# ppc_power.net
KiCad netlist of a schematic drawn in Altium Designer
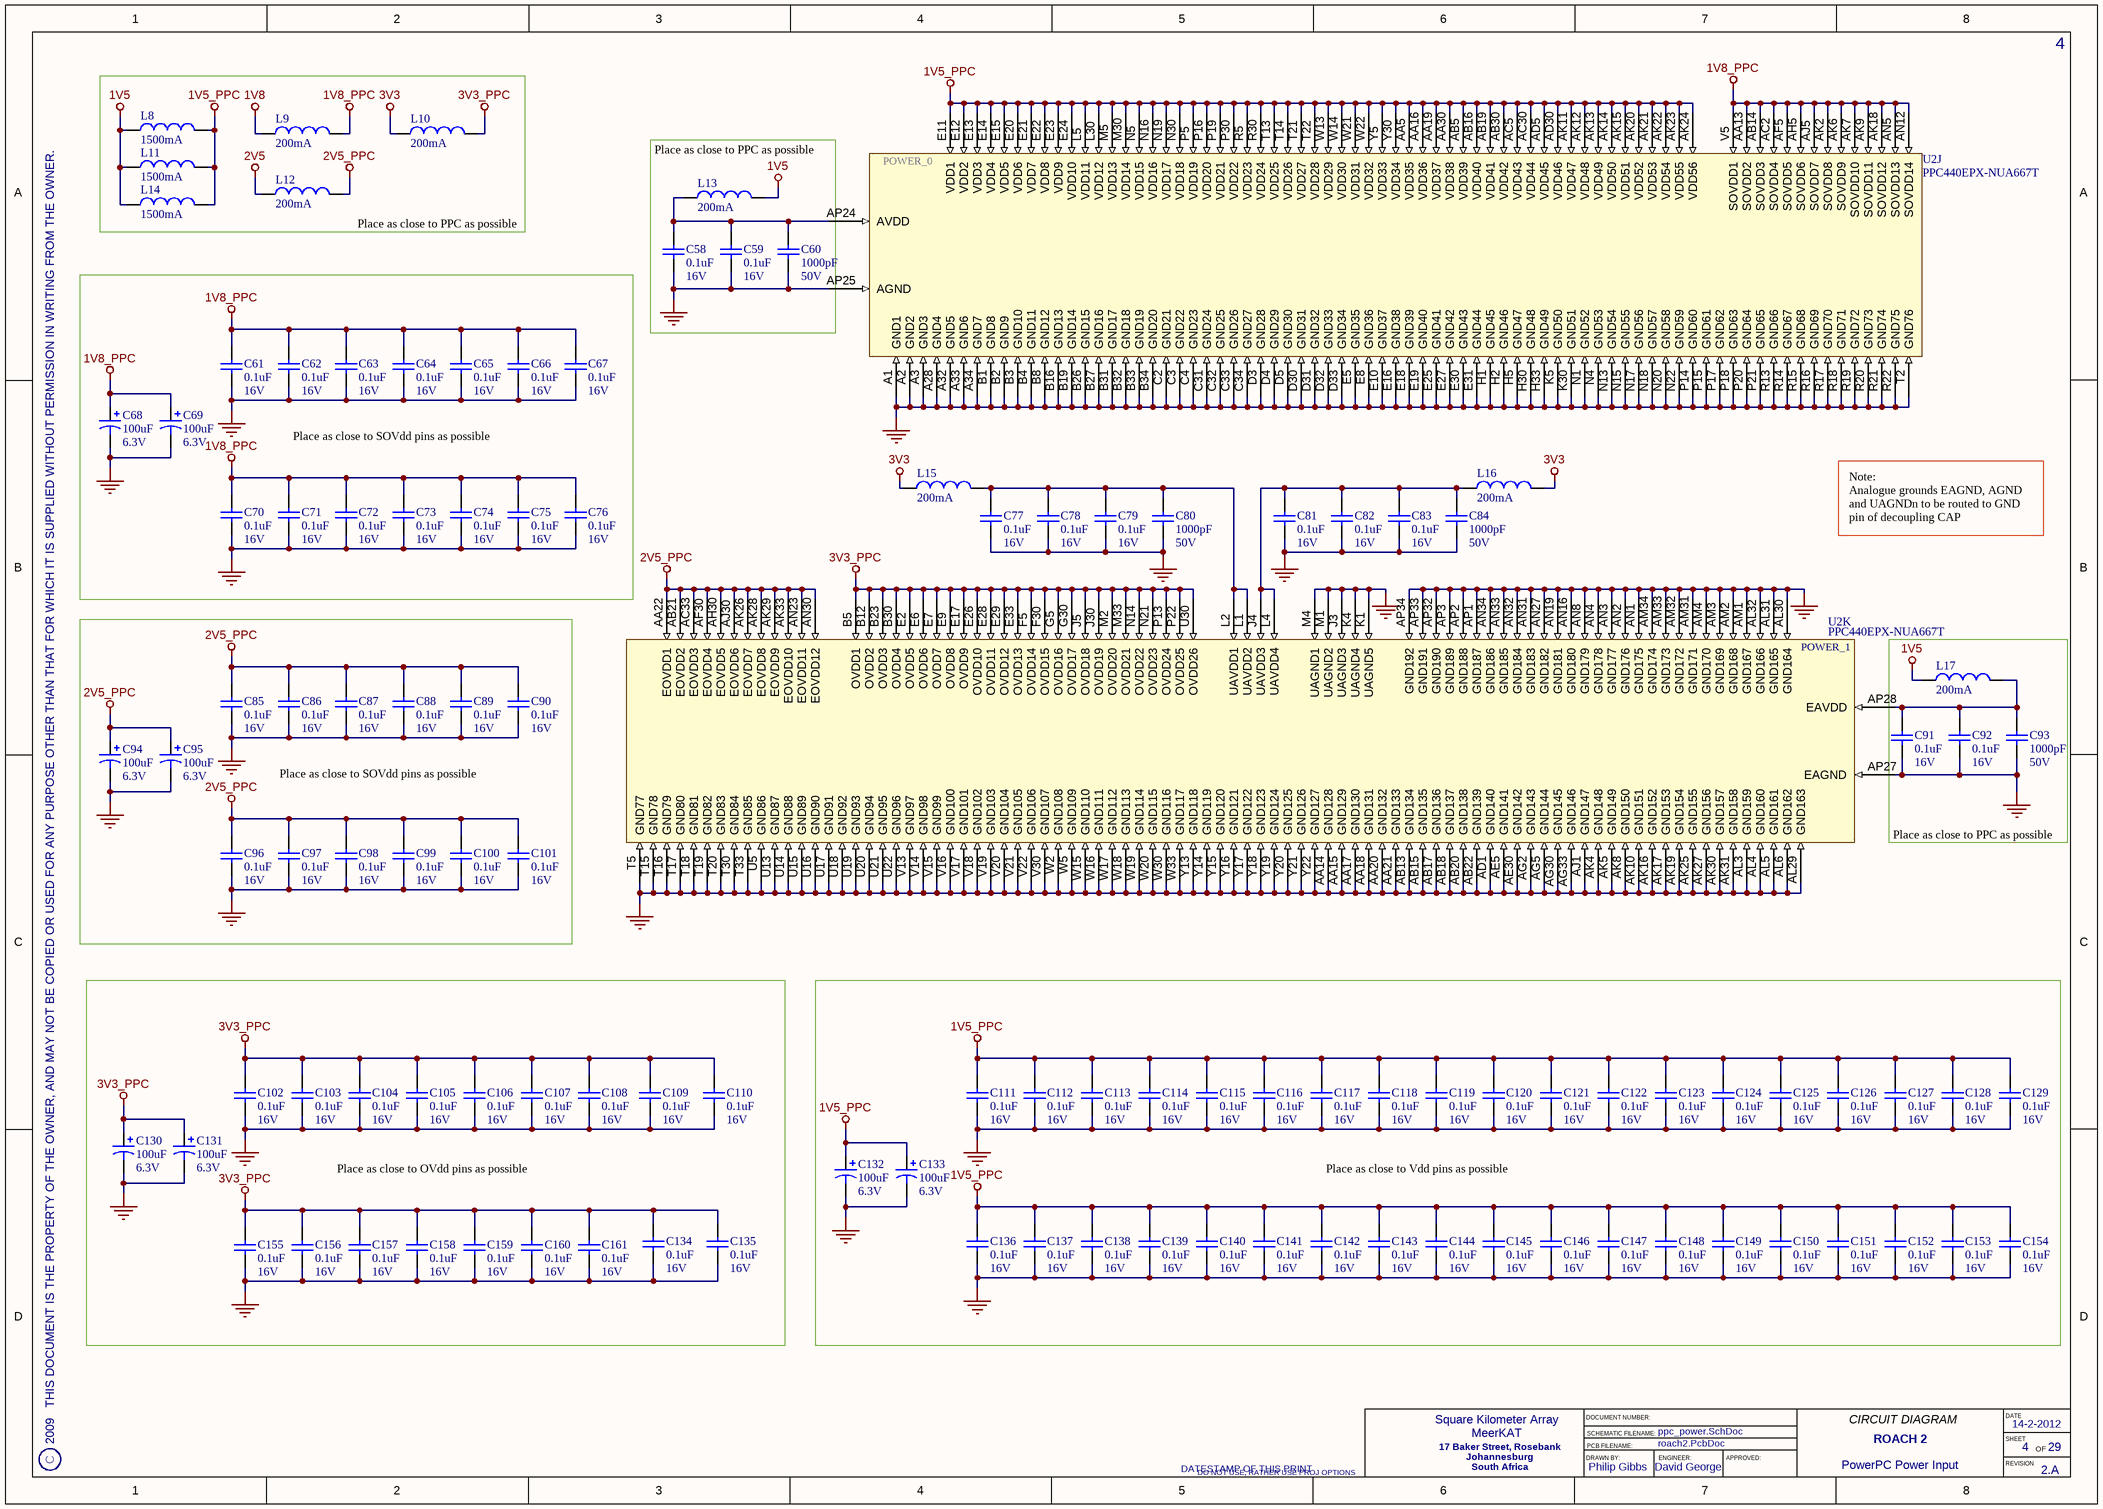
[diagram p0: ppc_power.SchDoc]

(export (version "E")
  (design (tool "Eeschema 10.0.6"))
  (components
    (comp (ref "C58")
      (value "0.1uF")
      (footprint "CAPC1005X60L")
      (description "0.1uF, Ceramic Capacitor")
      (fields
        (field (name "RATING") "16V")
        (field (name "MANUFACTURER") "VENKEL")
        (field (name "PARTNUM") "C0402X7R160-104KN")
      )
      (libsource (lib "altium_db") (part "CapStd"))
    )
    (comp (ref "C59")
      (value "0.1uF")
      (footprint "CAPC1005X60L")
      (description "0.1uF, Ceramic Capacitor")
      (fields
        (field (name "RATING") "16V")
        (field (name "MANUFACTURER") "VENKEL")
        (field (name "PARTNUM") "C0402X7R160-104KN")
      )
      (libsource (lib "altium_db") (part "CapStd"))
    )
    (comp (ref "C60")
      (value "1000pF")
      (footprint "CAPC1005X55L")
      (description "1000pF, Ceramic Capacitor")
      (fields
        (field (name "RATING") "50V")
        (field (name "MANUFACTURER") "MURATA")
        (field (name "PARTNUM") "GRM155R61H102KA01D")
      )
      (libsource (lib "altium_db") (part "CapStd"))
    )
    (comp (ref "C61")
      (value "0.1uF")
      (footprint "CAPC1005X60L")
      (description "0.1uF, Ceramic Capacitor")
      (fields
        (field (name "RATING") "16V")
        (field (name "MANUFACTURER") "VENKEL")
        (field (name "PARTNUM") "C0402X7R160-104KN")
      )
      (libsource (lib "altium_db") (part "CapStd"))
    )
    (comp (ref "C62")
      (value "0.1uF")
      (footprint "CAPC1005X60L")
      (description "0.1uF, Ceramic Capacitor")
      (fields
        (field (name "RATING") "16V")
        (field (name "MANUFACTURER") "VENKEL")
        (field (name "PARTNUM") "C0402X7R160-104KN")
      )
      (libsource (lib "altium_db") (part "CapStd"))
    )
    (comp (ref "C63")
      (value "0.1uF")
      (footprint "CAPC1005X60L")
      (description "0.1uF, Ceramic Capacitor")
      (fields
        (field (name "RATING") "16V")
        (field (name "MANUFACTURER") "VENKEL")
        (field (name "PARTNUM") "C0402X7R160-104KN")
      )
      (libsource (lib "altium_db") (part "CapStd"))
    )
    (comp (ref "C64")
      (value "0.1uF")
      (footprint "CAPC1005X60L")
      (description "0.1uF, Ceramic Capacitor")
      (fields
        (field (name "RATING") "16V")
        (field (name "MANUFACTURER") "VENKEL")
        (field (name "PARTNUM") "C0402X7R160-104KN")
      )
      (libsource (lib "altium_db") (part "CapStd"))
    )
    (comp (ref "C65")
      (value "0.1uF")
      (footprint "CAPC1005X60L")
      (description "0.1uF, Ceramic Capacitor")
      (fields
        (field (name "RATING") "16V")
        (field (name "MANUFACTURER") "VENKEL")
        (field (name "PARTNUM") "C0402X7R160-104KN")
      )
      (libsource (lib "altium_db") (part "CapStd"))
    )
    (comp (ref "C66")
      (value "0.1uF")
      (footprint "CAPC1005X60L")
      (description "0.1uF, Ceramic Capacitor")
      (fields
        (field (name "RATING") "16V")
        (field (name "MANUFACTURER") "VENKEL")
        (field (name "PARTNUM") "C0402X7R160-104KN")
      )
      (libsource (lib "altium_db") (part "CapStd"))
    )
    (comp (ref "C67")
      (value "0.1uF")
      (footprint "CAPC1005X60L")
      (description "0.1uF, Ceramic Capacitor")
      (fields
        (field (name "RATING") "16V")
        (field (name "MANUFACTURER") "VENKEL")
        (field (name "PARTNUM") "C0402X7R160-104KN")
      )
      (libsource (lib "altium_db") (part "CapStd"))
    )
    (comp (ref "C68")
      (value "100uF")
      (footprint "CAPMP3528X210L")
      (description "100uF, Low ESR, Tantalum Capacitor")
      (fields
        (field (name "RATING") "6.3V")
        (field (name "MANUFACTURER") "AVX")
        (field (name "PARTNUM") "TPSB107M006R0200")
      )
      (libsource (lib "altium_db") (part "CapPol"))
    )
    (comp (ref "C69")
      (value "100uF")
      (footprint "CAPMP3528X210L")
      (description "100uF, Low ESR, Tantalum Capacitor")
      (fields
        (field (name "RATING") "6.3V")
        (field (name "MANUFACTURER") "AVX")
        (field (name "PARTNUM") "TPSB107M006R0200")
      )
      (libsource (lib "altium_db") (part "CapPol"))
    )
    (comp (ref "C70")
      (value "0.1uF")
      (footprint "CAPC1005X60L")
      (description "0.1uF, Ceramic Capacitor")
      (fields
        (field (name "RATING") "16V")
        (field (name "MANUFACTURER") "VENKEL")
        (field (name "PARTNUM") "C0402X7R160-104KN")
      )
      (libsource (lib "altium_db") (part "CapStd"))
    )
    (comp (ref "C71")
      (value "0.1uF")
      (footprint "CAPC1005X60L")
      (description "0.1uF, Ceramic Capacitor")
      (fields
        (field (name "RATING") "16V")
        (field (name "MANUFACTURER") "VENKEL")
        (field (name "PARTNUM") "C0402X7R160-104KN")
      )
      (libsource (lib "altium_db") (part "CapStd"))
    )
    (comp (ref "C72")
      (value "0.1uF")
      (footprint "CAPC1005X60L")
      (description "0.1uF, Ceramic Capacitor")
      (fields
        (field (name "RATING") "16V")
        (field (name "MANUFACTURER") "VENKEL")
        (field (name "PARTNUM") "C0402X7R160-104KN")
      )
      (libsource (lib "altium_db") (part "CapStd"))
    )
    (comp (ref "C73")
      (value "0.1uF")
      (footprint "CAPC1005X60L")
      (description "0.1uF, Ceramic Capacitor")
      (fields
        (field (name "RATING") "16V")
        (field (name "MANUFACTURER") "VENKEL")
        (field (name "PARTNUM") "C0402X7R160-104KN")
      )
      (libsource (lib "altium_db") (part "CapStd"))
    )
    (comp (ref "C74")
      (value "0.1uF")
      (footprint "CAPC1005X60L")
      (description "0.1uF, Ceramic Capacitor")
      (fields
        (field (name "RATING") "16V")
        (field (name "MANUFACTURER") "VENKEL")
        (field (name "PARTNUM") "C0402X7R160-104KN")
      )
      (libsource (lib "altium_db") (part "CapStd"))
    )
    (comp (ref "C75")
      (value "0.1uF")
      (footprint "CAPC1005X60L")
      (description "0.1uF, Ceramic Capacitor")
      (fields
        (field (name "RATING") "16V")
        (field (name "MANUFACTURER") "VENKEL")
        (field (name "PARTNUM") "C0402X7R160-104KN")
      )
      (libsource (lib "altium_db") (part "CapStd"))
    )
    (comp (ref "C76")
      (value "0.1uF")
      (footprint "CAPC1005X60L")
      (description "0.1uF, Ceramic Capacitor")
      (fields
        (field (name "RATING") "16V")
        (field (name "MANUFACTURER") "VENKEL")
        (field (name "PARTNUM") "C0402X7R160-104KN")
      )
      (libsource (lib "altium_db") (part "CapStd"))
    )
    (comp (ref "C77")
      (value "0.1uF")
      (footprint "CAPC1005X60L")
      (description "0.1uF, Ceramic Capacitor")
      (fields
        (field (name "RATING") "16V")
        (field (name "MANUFACTURER") "VENKEL")
        (field (name "PARTNUM") "C0402X7R160-104KN")
      )
      (libsource (lib "altium_db") (part "CapStd"))
    )
    (comp (ref "C78")
      (value "0.1uF")
      (footprint "CAPC1005X60L")
      (description "0.1uF, Ceramic Capacitor")
      (fields
        (field (name "RATING") "16V")
        (field (name "MANUFACTURER") "VENKEL")
        (field (name "PARTNUM") "C0402X7R160-104KN")
      )
      (libsource (lib "altium_db") (part "CapStd"))
    )
    (comp (ref "C79")
      (value "0.1uF")
      (footprint "CAPC1005X60L")
      (description "0.1uF, Ceramic Capacitor")
      (fields
        (field (name "RATING") "16V")
        (field (name "MANUFACTURER") "VENKEL")
        (field (name "PARTNUM") "C0402X7R160-104KN")
      )
      (libsource (lib "altium_db") (part "CapStd"))
    )
    (comp (ref "C80")
      (value "1000pF")
      (footprint "CAPC1005X55L")
      (description "1000pF, Ceramic Capacitor")
      (fields
        (field (name "RATING") "50V")
        (field (name "MANUFACTURER") "MURATA")
        (field (name "PARTNUM") "GRM155R61H102KA01D")
      )
      (libsource (lib "altium_db") (part "CapStd"))
    )
    (comp (ref "C81")
      (value "0.1uF")
      (footprint "CAPC1005X60L")
      (description "0.1uF, Ceramic Capacitor")
      (fields
        (field (name "RATING") "16V")
        (field (name "MANUFACTURER") "VENKEL")
        (field (name "PARTNUM") "C0402X7R160-104KN")
      )
      (libsource (lib "altium_db") (part "CapStd"))
    )
    (comp (ref "C82")
      (value "0.1uF")
      (footprint "CAPC1005X60L")
      (description "0.1uF, Ceramic Capacitor")
      (fields
        (field (name "RATING") "16V")
        (field (name "MANUFACTURER") "VENKEL")
        (field (name "PARTNUM") "C0402X7R160-104KN")
      )
      (libsource (lib "altium_db") (part "CapStd"))
    )
    (comp (ref "C83")
      (value "0.1uF")
      (footprint "CAPC1005X60L")
      (description "0.1uF, Ceramic Capacitor")
      (fields
        (field (name "RATING") "16V")
        (field (name "MANUFACTURER") "VENKEL")
        (field (name "PARTNUM") "C0402X7R160-104KN")
      )
      (libsource (lib "altium_db") (part "CapStd"))
    )
    (comp (ref "C84")
      (value "1000pF")
      (footprint "CAPC1005X55L")
      (description "1000pF, Ceramic Capacitor")
      (fields
        (field (name "RATING") "50V")
        (field (name "MANUFACTURER") "MURATA")
        (field (name "PARTNUM") "GRM155R61H102KA01D")
      )
      (libsource (lib "altium_db") (part "CapStd"))
    )
    (comp (ref "C85")
      (value "0.1uF")
      (footprint "CAPC1005X60L")
      (description "0.1uF, Ceramic Capacitor")
      (fields
        (field (name "RATING") "16V")
        (field (name "MANUFACTURER") "VENKEL")
        (field (name "PARTNUM") "C0402X7R160-104KN")
      )
      (libsource (lib "altium_db") (part "CapStd"))
    )
    (comp (ref "C86")
      (value "0.1uF")
      (footprint "CAPC1005X60L")
      (description "0.1uF, Ceramic Capacitor")
      (fields
        (field (name "RATING") "16V")
        (field (name "MANUFACTURER") "VENKEL")
        (field (name "PARTNUM") "C0402X7R160-104KN")
      )
      (libsource (lib "altium_db") (part "CapStd"))
    )
    (comp (ref "C87")
      (value "0.1uF")
      (footprint "CAPC1005X60L")
      (description "0.1uF, Ceramic Capacitor")
      (fields
        (field (name "RATING") "16V")
        (field (name "MANUFACTURER") "VENKEL")
        (field (name "PARTNUM") "C0402X7R160-104KN")
      )
      (libsource (lib "altium_db") (part "CapStd"))
    )
    (comp (ref "C88")
      (value "0.1uF")
      (footprint "CAPC1005X60L")
      (description "0.1uF, Ceramic Capacitor")
      (fields
        (field (name "RATING") "16V")
        (field (name "MANUFACTURER") "VENKEL")
        (field (name "PARTNUM") "C0402X7R160-104KN")
      )
      (libsource (lib "altium_db") (part "CapStd"))
    )
    (comp (ref "C89")
      (value "0.1uF")
      (footprint "CAPC1005X60L")
      (description "0.1uF, Ceramic Capacitor")
      (fields
        (field (name "RATING") "16V")
        (field (name "MANUFACTURER") "VENKEL")
        (field (name "PARTNUM") "C0402X7R160-104KN")
      )
      (libsource (lib "altium_db") (part "CapStd"))
    )
    (comp (ref "C90")
      (value "0.1uF")
      (footprint "CAPC1005X60L")
      (description "0.1uF, Ceramic Capacitor")
      (fields
        (field (name "RATING") "16V")
        (field (name "MANUFACTURER") "VENKEL")
        (field (name "PARTNUM") "C0402X7R160-104KN")
      )
      (libsource (lib "altium_db") (part "CapStd"))
    )
    (comp (ref "C91")
      (value "0.1uF")
      (footprint "CAPC1005X60L")
      (description "0.1uF, Ceramic Capacitor")
      (fields
        (field (name "RATING") "16V")
        (field (name "MANUFACTURER") "VENKEL")
        (field (name "PARTNUM") "C0402X7R160-104KN")
      )
      (libsource (lib "altium_db") (part "CapStd"))
    )
    (comp (ref "C92")
      (value "0.1uF")
      (footprint "CAPC1005X60L")
      (description "0.1uF, Ceramic Capacitor")
      (fields
        (field (name "RATING") "16V")
        (field (name "MANUFACTURER") "VENKEL")
        (field (name "PARTNUM") "C0402X7R160-104KN")
      )
      (libsource (lib "altium_db") (part "CapStd"))
    )
    (comp (ref "C93")
      (value "1000pF")
      (footprint "CAPC1005X55L")
      (description "1000pF, Ceramic Capacitor")
      (fields
        (field (name "RATING") "50V")
        (field (name "MANUFACTURER") "MURATA")
        (field (name "PARTNUM") "GRM155R61H102KA01D")
      )
      (libsource (lib "altium_db") (part "CapStd"))
    )
    (comp (ref "C94")
      (value "100uF")
      (footprint "CAPMP3528X210L")
      (description "100uF, Low ESR, Tantalum Capacitor")
      (fields
        (field (name "RATING") "6.3V")
        (field (name "MANUFACTURER") "AVX")
        (field (name "PARTNUM") "TPSB107M006R0200")
      )
      (libsource (lib "altium_db") (part "CapPol"))
    )
    (comp (ref "C95")
      (value "100uF")
      (footprint "CAPMP3528X210L")
      (description "100uF, Low ESR, Tantalum Capacitor")
      (fields
        (field (name "RATING") "6.3V")
        (field (name "MANUFACTURER") "AVX")
        (field (name "PARTNUM") "TPSB107M006R0200")
      )
      (libsource (lib "altium_db") (part "CapPol"))
    )
    (comp (ref "C96")
      (value "0.1uF")
      (footprint "CAPC1005X60L")
      (description "0.1uF, Ceramic Capacitor")
      (fields
        (field (name "RATING") "16V")
        (field (name "MANUFACTURER") "VENKEL")
        (field (name "PARTNUM") "C0402X7R160-104KN")
      )
      (libsource (lib "altium_db") (part "CapStd"))
    )
    (comp (ref "C97")
      (value "0.1uF")
      (footprint "CAPC1005X60L")
      (description "0.1uF, Ceramic Capacitor")
      (fields
        (field (name "RATING") "16V")
        (field (name "MANUFACTURER") "VENKEL")
        (field (name "PARTNUM") "C0402X7R160-104KN")
      )
      (libsource (lib "altium_db") (part "CapStd"))
    )
    (comp (ref "C98")
      (value "0.1uF")
      (footprint "CAPC1005X60L")
      (description "0.1uF, Ceramic Capacitor")
      (fields
        (field (name "RATING") "16V")
        (field (name "MANUFACTURER") "VENKEL")
        (field (name "PARTNUM") "C0402X7R160-104KN")
      )
      (libsource (lib "altium_db") (part "CapStd"))
    )
    (comp (ref "C99")
      (value "0.1uF")
      (footprint "CAPC1005X60L")
      (description "0.1uF, Ceramic Capacitor")
      (fields
        (field (name "RATING") "16V")
        (field (name "MANUFACTURER") "VENKEL")
        (field (name "PARTNUM") "C0402X7R160-104KN")
      )
      (libsource (lib "altium_db") (part "CapStd"))
    )
    (comp (ref "C100")
      (value "0.1uF")
      (footprint "CAPC1005X60L")
      (description "0.1uF, Ceramic Capacitor")
      (fields
        (field (name "RATING") "16V")
        (field (name "MANUFACTURER") "VENKEL")
        (field (name "PARTNUM") "C0402X7R160-104KN")
      )
      (libsource (lib "altium_db") (part "CapStd"))
    )
    (comp (ref "C101")
      (value "0.1uF")
      (footprint "CAPC1005X60L")
      (description "0.1uF, Ceramic Capacitor")
      (fields
        (field (name "RATING") "16V")
        (field (name "MANUFACTURER") "VENKEL")
        (field (name "PARTNUM") "C0402X7R160-104KN")
      )
      (libsource (lib "altium_db") (part "CapStd"))
    )
    (comp (ref "C102")
      (value "0.1uF")
      (footprint "CAPC1005X60L")
      (description "0.1uF, Ceramic Capacitor")
      (fields
        (field (name "RATING") "16V")
        (field (name "MANUFACTURER") "VENKEL")
        (field (name "PARTNUM") "C0402X7R160-104KN")
      )
      (libsource (lib "altium_db") (part "CapStd"))
    )
    (comp (ref "C103")
      (value "0.1uF")
      (footprint "CAPC1005X60L")
      (description "0.1uF, Ceramic Capacitor")
      (fields
        (field (name "RATING") "16V")
        (field (name "MANUFACTURER") "VENKEL")
        (field (name "PARTNUM") "C0402X7R160-104KN")
      )
      (libsource (lib "altium_db") (part "CapStd"))
    )
    (comp (ref "C104")
      (value "0.1uF")
      (footprint "CAPC1005X60L")
      (description "0.1uF, Ceramic Capacitor")
      (fields
        (field (name "RATING") "16V")
        (field (name "MANUFACTURER") "VENKEL")
        (field (name "PARTNUM") "C0402X7R160-104KN")
      )
      (libsource (lib "altium_db") (part "CapStd"))
    )
    (comp (ref "C105")
      (value "0.1uF")
      (footprint "CAPC1005X60L")
      (description "0.1uF, Ceramic Capacitor")
      (fields
        (field (name "RATING") "16V")
        (field (name "MANUFACTURER") "VENKEL")
        (field (name "PARTNUM") "C0402X7R160-104KN")
      )
      (libsource (lib "altium_db") (part "CapStd"))
    )
    (comp (ref "C106")
      (value "0.1uF")
      (footprint "CAPC1005X60L")
      (description "0.1uF, Ceramic Capacitor")
      (fields
        (field (name "RATING") "16V")
        (field (name "MANUFACTURER") "VENKEL")
        (field (name "PARTNUM") "C0402X7R160-104KN")
      )
      (libsource (lib "altium_db") (part "CapStd"))
    )
    (comp (ref "C107")
      (value "0.1uF")
      (footprint "CAPC1005X60L")
      (description "0.1uF, Ceramic Capacitor")
      (fields
        (field (name "RATING") "16V")
        (field (name "MANUFACTURER") "VENKEL")
        (field (name "PARTNUM") "C0402X7R160-104KN")
      )
      (libsource (lib "altium_db") (part "CapStd"))
    )
    (comp (ref "C108")
      (value "0.1uF")
      (footprint "CAPC1005X60L")
      (description "0.1uF, Ceramic Capacitor")
      (fields
        (field (name "RATING") "16V")
        (field (name "MANUFACTURER") "VENKEL")
        (field (name "PARTNUM") "C0402X7R160-104KN")
      )
      (libsource (lib "altium_db") (part "CapStd"))
    )
    (comp (ref "C109")
      (value "0.1uF")
      (footprint "CAPC1005X60L")
      (description "0.1uF, Ceramic Capacitor")
      (fields
        (field (name "RATING") "16V")
        (field (name "MANUFACTURER") "VENKEL")
        (field (name "PARTNUM") "C0402X7R160-104KN")
      )
      (libsource (lib "altium_db") (part "CapStd"))
    )
    (comp (ref "C110")
      (value "0.1uF")
      (footprint "CAPC1005X60L")
      (description "0.1uF, Ceramic Capacitor")
      (fields
        (field (name "RATING") "16V")
        (field (name "MANUFACTURER") "VENKEL")
        (field (name "PARTNUM") "C0402X7R160-104KN")
      )
      (libsource (lib "altium_db") (part "CapStd"))
    )
    (comp (ref "C111")
      (value "0.1uF")
      (footprint "CAPC1005X60L")
      (description "0.1uF, Ceramic Capacitor")
      (fields
        (field (name "RATING") "16V")
        (field (name "MANUFACTURER") "VENKEL")
        (field (name "PARTNUM") "C0402X7R160-104KN")
      )
      (libsource (lib "altium_db") (part "CapStd"))
    )
    (comp (ref "C112")
      (value "0.1uF")
      (footprint "CAPC1005X60L")
      (description "0.1uF, Ceramic Capacitor")
      (fields
        (field (name "RATING") "16V")
        (field (name "MANUFACTURER") "VENKEL")
        (field (name "PARTNUM") "C0402X7R160-104KN")
      )
      (libsource (lib "altium_db") (part "CapStd"))
    )
    (comp (ref "C113")
      (value "0.1uF")
      (footprint "CAPC1005X60L")
      (description "0.1uF, Ceramic Capacitor")
      (fields
        (field (name "RATING") "16V")
        (field (name "MANUFACTURER") "VENKEL")
        (field (name "PARTNUM") "C0402X7R160-104KN")
      )
      (libsource (lib "altium_db") (part "CapStd"))
    )
    (comp (ref "C114")
      (value "0.1uF")
      (footprint "CAPC1005X60L")
      (description "0.1uF, Ceramic Capacitor")
      (fields
        (field (name "RATING") "16V")
        (field (name "MANUFACTURER") "VENKEL")
        (field (name "PARTNUM") "C0402X7R160-104KN")
      )
      (libsource (lib "altium_db") (part "CapStd"))
    )
    (comp (ref "C115")
      (value "0.1uF")
      (footprint "CAPC1005X60L")
      (description "0.1uF, Ceramic Capacitor")
      (fields
        (field (name "RATING") "16V")
        (field (name "MANUFACTURER") "VENKEL")
        (field (name "PARTNUM") "C0402X7R160-104KN")
      )
      (libsource (lib "altium_db") (part "CapStd"))
    )
    (comp (ref "C116")
      (value "0.1uF")
      (footprint "CAPC1005X60L")
      (description "0.1uF, Ceramic Capacitor")
      (fields
        (field (name "RATING") "16V")
        (field (name "MANUFACTURER") "VENKEL")
        (field (name "PARTNUM") "C0402X7R160-104KN")
      )
      (libsource (lib "altium_db") (part "CapStd"))
    )
    (comp (ref "C117")
      (value "0.1uF")
      (footprint "CAPC1005X60L")
      (description "0.1uF, Ceramic Capacitor")
      (fields
        (field (name "RATING") "16V")
        (field (name "MANUFACTURER") "VENKEL")
        (field (name "PARTNUM") "C0402X7R160-104KN")
      )
      (libsource (lib "altium_db") (part "CapStd"))
    )
    (comp (ref "C118")
      (value "0.1uF")
      (footprint "CAPC1005X60L")
      (description "0.1uF, Ceramic Capacitor")
      (fields
        (field (name "RATING") "16V")
        (field (name "MANUFACTURER") "VENKEL")
        (field (name "PARTNUM") "C0402X7R160-104KN")
      )
      (libsource (lib "altium_db") (part "CapStd"))
    )
    (comp (ref "C119")
      (value "0.1uF")
      (footprint "CAPC1005X60L")
      (description "0.1uF, Ceramic Capacitor")
      (fields
        (field (name "RATING") "16V")
        (field (name "MANUFACTURER") "VENKEL")
        (field (name "PARTNUM") "C0402X7R160-104KN")
      )
      (libsource (lib "altium_db") (part "CapStd"))
    )
    (comp (ref "C120")
      (value "0.1uF")
      (footprint "CAPC1005X60L")
      (description "0.1uF, Ceramic Capacitor")
      (fields
        (field (name "RATING") "16V")
        (field (name "MANUFACTURER") "VENKEL")
        (field (name "PARTNUM") "C0402X7R160-104KN")
      )
      (libsource (lib "altium_db") (part "CapStd"))
    )
    (comp (ref "C121")
      (value "0.1uF")
      (footprint "CAPC1005X60L")
      (description "0.1uF, Ceramic Capacitor")
      (fields
        (field (name "RATING") "16V")
        (field (name "MANUFACTURER") "VENKEL")
        (field (name "PARTNUM") "C0402X7R160-104KN")
      )
      (libsource (lib "altium_db") (part "CapStd"))
    )
    (comp (ref "C122")
      (value "0.1uF")
      (footprint "CAPC1005X60L")
      (description "0.1uF, Ceramic Capacitor")
      (fields
        (field (name "RATING") "16V")
        (field (name "MANUFACTURER") "VENKEL")
        (field (name "PARTNUM") "C0402X7R160-104KN")
      )
      (libsource (lib "altium_db") (part "CapStd"))
    )
    (comp (ref "C123")
      (value "0.1uF")
      (footprint "CAPC1005X60L")
      (description "0.1uF, Ceramic Capacitor")
      (fields
        (field (name "RATING") "16V")
        (field (name "MANUFACTURER") "VENKEL")
        (field (name "PARTNUM") "C0402X7R160-104KN")
      )
      (libsource (lib "altium_db") (part "CapStd"))
    )
    (comp (ref "C124")
      (value "0.1uF")
      (footprint "CAPC1005X60L")
      (description "0.1uF, Ceramic Capacitor")
      (fields
        (field (name "RATING") "16V")
        (field (name "MANUFACTURER") "VENKEL")
        (field (name "PARTNUM") "C0402X7R160-104KN")
      )
      (libsource (lib "altium_db") (part "CapStd"))
    )
    (comp (ref "C125")
      (value "0.1uF")
      (footprint "CAPC1005X60L")
      (description "0.1uF, Ceramic Capacitor")
      (fields
        (field (name "RATING") "16V")
        (field (name "MANUFACTURER") "VENKEL")
        (field (name "PARTNUM") "C0402X7R160-104KN")
      )
      (libsource (lib "altium_db") (part "CapStd"))
    )
    (comp (ref "C126")
      (value "0.1uF")
      (footprint "CAPC1005X60L")
      (description "0.1uF, Ceramic Capacitor")
      (fields
        (field (name "RATING") "16V")
        (field (name "MANUFACTURER") "VENKEL")
        (field (name "PARTNUM") "C0402X7R160-104KN")
      )
      (libsource (lib "altium_db") (part "CapStd"))
    )
    (comp (ref "C127")
      (value "0.1uF")
      (footprint "CAPC1005X60L")
      (description "0.1uF, Ceramic Capacitor")
      (fields
        (field (name "RATING") "16V")
        (field (name "MANUFACTURER") "VENKEL")
        (field (name "PARTNUM") "C0402X7R160-104KN")
      )
      (libsource (lib "altium_db") (part "CapStd"))
    )
    (comp (ref "C128")
      (value "0.1uF")
      (footprint "CAPC1005X60L")
      (description "0.1uF, Ceramic Capacitor")
      (fields
        (field (name "RATING") "16V")
        (field (name "MANUFACTURER") "VENKEL")
        (field (name "PARTNUM") "C0402X7R160-104KN")
      )
      (libsource (lib "altium_db") (part "CapStd"))
    )
    (comp (ref "C129")
      (value "0.1uF")
      (footprint "CAPC1005X60L")
      (description "0.1uF, Ceramic Capacitor")
      (fields
        (field (name "RATING") "16V")
        (field (name "MANUFACTURER") "VENKEL")
        (field (name "PARTNUM") "C0402X7R160-104KN")
      )
      (libsource (lib "altium_db") (part "CapStd"))
    )
    (comp (ref "C130")
      (value "100uF")
      (footprint "CAPMP3528X210L")
      (description "100uF, Low ESR, Tantalum Capacitor")
      (fields
        (field (name "RATING") "6.3V")
        (field (name "MANUFACTURER") "AVX")
        (field (name "PARTNUM") "TPSB107M006R0200")
      )
      (libsource (lib "altium_db") (part "CapPol"))
    )
    (comp (ref "C131")
      (value "100uF")
      (footprint "CAPMP3528X210L")
      (description "100uF, Low ESR, Tantalum Capacitor")
      (fields
        (field (name "RATING") "6.3V")
        (field (name "MANUFACTURER") "AVX")
        (field (name "PARTNUM") "TPSB107M006R0200")
      )
      (libsource (lib "altium_db") (part "CapPol"))
    )
    (comp (ref "C132")
      (value "100uF")
      (footprint "CAPMP3528X210L")
      (description "100uF, Low ESR, Tantalum Capacitor")
      (fields
        (field (name "RATING") "6.3V")
        (field (name "MANUFACTURER") "AVX")
        (field (name "PARTNUM") "TPSB107M006R0200")
      )
      (libsource (lib "altium_db") (part "CapPol"))
    )
    (comp (ref "C133")
      (value "100uF")
      (footprint "CAPMP3528X210L")
      (description "100uF, Low ESR, Tantalum Capacitor")
      (fields
        (field (name "RATING") "6.3V")
        (field (name "MANUFACTURER") "AVX")
        (field (name "PARTNUM") "TPSB107M006R0200")
      )
      (libsource (lib "altium_db") (part "CapPol"))
    )
    (comp (ref "C134")
      (value "0.1uF")
      (footprint "CAPC1005X60L")
      (description "0.1uF, Ceramic Capacitor")
      (fields
        (field (name "RATING") "16V")
        (field (name "MANUFACTURER") "VENKEL")
        (field (name "PARTNUM") "C0402X7R160-104KN")
      )
      (libsource (lib "altium_db") (part "CapStd"))
    )
    (comp (ref "C135")
      (value "0.1uF")
      (footprint "CAPC1005X60L")
      (description "0.1uF, Ceramic Capacitor")
      (fields
        (field (name "RATING") "16V")
        (field (name "MANUFACTURER") "VENKEL")
        (field (name "PARTNUM") "C0402X7R160-104KN")
      )
      (libsource (lib "altium_db") (part "CapStd"))
    )
    (comp (ref "C136")
      (value "0.1uF")
      (footprint "CAPC1005X60L")
      (description "0.1uF, Ceramic Capacitor")
      (fields
        (field (name "RATING") "16V")
        (field (name "MANUFACTURER") "VENKEL")
        (field (name "PARTNUM") "C0402X7R160-104KN")
      )
      (libsource (lib "altium_db") (part "CapStd"))
    )
    (comp (ref "C137")
      (value "0.1uF")
      (footprint "CAPC1005X60L")
      (description "0.1uF, Ceramic Capacitor")
      (fields
        (field (name "RATING") "16V")
        (field (name "MANUFACTURER") "VENKEL")
        (field (name "PARTNUM") "C0402X7R160-104KN")
      )
      (libsource (lib "altium_db") (part "CapStd"))
    )
    (comp (ref "C138")
      (value "0.1uF")
      (footprint "CAPC1005X60L")
      (description "0.1uF, Ceramic Capacitor")
      (fields
        (field (name "RATING") "16V")
        (field (name "MANUFACTURER") "VENKEL")
        (field (name "PARTNUM") "C0402X7R160-104KN")
      )
      (libsource (lib "altium_db") (part "CapStd"))
    )
    (comp (ref "C139")
      (value "0.1uF")
      (footprint "CAPC1005X60L")
      (description "0.1uF, Ceramic Capacitor")
      (fields
        (field (name "RATING") "16V")
        (field (name "MANUFACTURER") "VENKEL")
        (field (name "PARTNUM") "C0402X7R160-104KN")
      )
      (libsource (lib "altium_db") (part "CapStd"))
    )
    (comp (ref "C140")
      (value "0.1uF")
      (footprint "CAPC1005X60L")
      (description "0.1uF, Ceramic Capacitor")
      (fields
        (field (name "RATING") "16V")
        (field (name "MANUFACTURER") "VENKEL")
        (field (name "PARTNUM") "C0402X7R160-104KN")
      )
      (libsource (lib "altium_db") (part "CapStd"))
    )
    (comp (ref "C141")
      (value "0.1uF")
      (footprint "CAPC1005X60L")
      (description "0.1uF, Ceramic Capacitor")
      (fields
        (field (name "RATING") "16V")
        (field (name "MANUFACTURER") "VENKEL")
        (field (name "PARTNUM") "C0402X7R160-104KN")
      )
      (libsource (lib "altium_db") (part "CapStd"))
    )
    (comp (ref "C142")
      (value "0.1uF")
      (footprint "CAPC1005X60L")
      (description "0.1uF, Ceramic Capacitor")
      (fields
        (field (name "RATING") "16V")
        (field (name "MANUFACTURER") "VENKEL")
        (field (name "PARTNUM") "C0402X7R160-104KN")
      )
      (libsource (lib "altium_db") (part "CapStd"))
    )
    (comp (ref "C143")
      (value "0.1uF")
      (footprint "CAPC1005X60L")
      (description "0.1uF, Ceramic Capacitor")
      (fields
        (field (name "RATING") "16V")
        (field (name "MANUFACTURER") "VENKEL")
        (field (name "PARTNUM") "C0402X7R160-104KN")
      )
      (libsource (lib "altium_db") (part "CapStd"))
    )
    (comp (ref "C144")
      (value "0.1uF")
      (footprint "CAPC1005X60L")
      (description "0.1uF, Ceramic Capacitor")
      (fields
        (field (name "RATING") "16V")
        (field (name "MANUFACTURER") "VENKEL")
        (field (name "PARTNUM") "C0402X7R160-104KN")
      )
      (libsource (lib "altium_db") (part "CapStd"))
    )
    (comp (ref "C145")
      (value "0.1uF")
      (footprint "CAPC1005X60L")
      (description "0.1uF, Ceramic Capacitor")
      (fields
        (field (name "RATING") "16V")
        (field (name "MANUFACTURER") "VENKEL")
        (field (name "PARTNUM") "C0402X7R160-104KN")
      )
      (libsource (lib "altium_db") (part "CapStd"))
    )
    (comp (ref "C146")
      (value "0.1uF")
      (footprint "CAPC1005X60L")
      (description "0.1uF, Ceramic Capacitor")
      (fields
        (field (name "RATING") "16V")
        (field (name "MANUFACTURER") "VENKEL")
        (field (name "PARTNUM") "C0402X7R160-104KN")
      )
      (libsource (lib "altium_db") (part "CapStd"))
    )
    (comp (ref "C147")
      (value "0.1uF")
      (footprint "CAPC1005X60L")
      (description "0.1uF, Ceramic Capacitor")
      (fields
        (field (name "RATING") "16V")
        (field (name "MANUFACTURER") "VENKEL")
        (field (name "PARTNUM") "C0402X7R160-104KN")
      )
      (libsource (lib "altium_db") (part "CapStd"))
    )
    (comp (ref "C148")
      (value "0.1uF")
      (footprint "CAPC1005X60L")
      (description "0.1uF, Ceramic Capacitor")
      (fields
        (field (name "RATING") "16V")
        (field (name "MANUFACTURER") "VENKEL")
        (field (name "PARTNUM") "C0402X7R160-104KN")
      )
      (libsource (lib "altium_db") (part "CapStd"))
    )
    (comp (ref "C149")
      (value "0.1uF")
      (footprint "CAPC1005X60L")
      (description "0.1uF, Ceramic Capacitor")
      (fields
        (field (name "RATING") "16V")
        (field (name "MANUFACTURER") "VENKEL")
        (field (name "PARTNUM") "C0402X7R160-104KN")
      )
      (libsource (lib "altium_db") (part "CapStd"))
    )
    (comp (ref "C150")
      (value "0.1uF")
      (footprint "CAPC1005X60L")
      (description "0.1uF, Ceramic Capacitor")
      (fields
        (field (name "RATING") "16V")
        (field (name "MANUFACTURER") "VENKEL")
        (field (name "PARTNUM") "C0402X7R160-104KN")
      )
      (libsource (lib "altium_db") (part "CapStd"))
    )
    (comp (ref "C151")
      (value "0.1uF")
      (footprint "CAPC1005X60L")
      (description "0.1uF, Ceramic Capacitor")
      (fields
        (field (name "RATING") "16V")
        (field (name "MANUFACTURER") "VENKEL")
        (field (name "PARTNUM") "C0402X7R160-104KN")
      )
      (libsource (lib "altium_db") (part "CapStd"))
    )
    (comp (ref "C152")
      (value "0.1uF")
      (footprint "CAPC1005X60L")
      (description "0.1uF, Ceramic Capacitor")
      (fields
        (field (name "RATING") "16V")
        (field (name "MANUFACTURER") "VENKEL")
        (field (name "PARTNUM") "C0402X7R160-104KN")
      )
      (libsource (lib "altium_db") (part "CapStd"))
    )
    (comp (ref "C153")
      (value "0.1uF")
      (footprint "CAPC1005X60L")
      (description "0.1uF, Ceramic Capacitor")
      (fields
        (field (name "RATING") "16V")
        (field (name "MANUFACTURER") "VENKEL")
        (field (name "PARTNUM") "C0402X7R160-104KN")
      )
      (libsource (lib "altium_db") (part "CapStd"))
    )
    (comp (ref "C154")
      (value "0.1uF")
      (footprint "CAPC1005X60L")
      (description "0.1uF, Ceramic Capacitor")
      (fields
        (field (name "RATING") "16V")
        (field (name "MANUFACTURER") "VENKEL")
        (field (name "PARTNUM") "C0402X7R160-104KN")
      )
      (libsource (lib "altium_db") (part "CapStd"))
    )
    (comp (ref "C155")
      (value "0.1uF")
      (footprint "CAPC1005X60L")
      (description "0.1uF, Ceramic Capacitor")
      (fields
        (field (name "RATING") "16V")
        (field (name "MANUFACTURER") "VENKEL")
        (field (name "PARTNUM") "C0402X7R160-104KN")
      )
      (libsource (lib "altium_db") (part "CapStd"))
    )
    (comp (ref "C156")
      (value "0.1uF")
      (footprint "CAPC1005X60L")
      (description "0.1uF, Ceramic Capacitor")
      (fields
        (field (name "RATING") "16V")
        (field (name "MANUFACTURER") "VENKEL")
        (field (name "PARTNUM") "C0402X7R160-104KN")
      )
      (libsource (lib "altium_db") (part "CapStd"))
    )
    (comp (ref "C157")
      (value "0.1uF")
      (footprint "CAPC1005X60L")
      (description "0.1uF, Ceramic Capacitor")
      (fields
        (field (name "RATING") "16V")
        (field (name "MANUFACTURER") "VENKEL")
        (field (name "PARTNUM") "C0402X7R160-104KN")
      )
      (libsource (lib "altium_db") (part "CapStd"))
    )
    (comp (ref "C158")
      (value "0.1uF")
      (footprint "CAPC1005X60L")
      (description "0.1uF, Ceramic Capacitor")
      (fields
        (field (name "RATING") "16V")
        (field (name "MANUFACTURER") "VENKEL")
        (field (name "PARTNUM") "C0402X7R160-104KN")
      )
      (libsource (lib "altium_db") (part "CapStd"))
    )
    (comp (ref "C159")
      (value "0.1uF")
      (footprint "CAPC1005X60L")
      (description "0.1uF, Ceramic Capacitor")
      (fields
        (field (name "RATING") "16V")
        (field (name "MANUFACTURER") "VENKEL")
        (field (name "PARTNUM") "C0402X7R160-104KN")
      )
      (libsource (lib "altium_db") (part "CapStd"))
    )
    (comp (ref "C160")
      (value "0.1uF")
      (footprint "CAPC1005X60L")
      (description "0.1uF, Ceramic Capacitor")
      (fields
        (field (name "RATING") "16V")
        (field (name "MANUFACTURER") "VENKEL")
        (field (name "PARTNUM") "C0402X7R160-104KN")
      )
      (libsource (lib "altium_db") (part "CapStd"))
    )
    (comp (ref "C161")
      (value "0.1uF")
      (footprint "CAPC1005X60L")
      (description "0.1uF, Ceramic Capacitor")
      (fields
        (field (name "RATING") "16V")
        (field (name "MANUFACTURER") "VENKEL")
        (field (name "PARTNUM") "C0402X7R160-104KN")
      )
      (libsource (lib "altium_db") (part "CapStd"))
    )
    (comp (ref "L8")
      (value "180R")
      (footprint "INDC1608X130L")
      (description "180 Ohm, Chip Ferrite Brad")
      (fields
        (field (name "RATING") "1500mA")
        (field (name "MANUFACTURER") "Murata")
        (field (name "PARTNUM") "BLM18PG181SN1")
      )
      (libsource (lib "altium_db") (part "IndStd"))
    )
    (comp (ref "L9")
      (value "600R")
      (footprint "INDC2012X130L")
      (description "600 Ohm, Chip Ferrite Bead")
      (fields
        (field (name "RATING") "200mA")
        (field (name "MANUFACTURER") "Murata")
        (field (name "PARTNUM") "BLM21BD601SN1")
      )
      (libsource (lib "altium_db") (part "IndStd"))
    )
    (comp (ref "L10")
      (value "600R")
      (footprint "INDC2012X130L")
      (description "600 Ohm, Chip Ferrite Bead")
      (fields
        (field (name "RATING") "200mA")
        (field (name "MANUFACTURER") "Murata")
        (field (name "PARTNUM") "BLM21BD601SN1")
      )
      (libsource (lib "altium_db") (part "IndStd"))
    )
    (comp (ref "L11")
      (value "180R")
      (footprint "INDC1608X130L")
      (description "180 Ohm, Chip Ferrite Brad")
      (fields
        (field (name "RATING") "1500mA")
        (field (name "MANUFACTURER") "Murata")
        (field (name "PARTNUM") "BLM18PG181SN1")
      )
      (libsource (lib "altium_db") (part "IndStd"))
    )
    (comp (ref "L12")
      (value "600R")
      (footprint "INDC2012X130L")
      (description "600 Ohm, Chip Ferrite Bead")
      (fields
        (field (name "RATING") "200mA")
        (field (name "MANUFACTURER") "Murata")
        (field (name "PARTNUM") "BLM21BD601SN1")
      )
      (libsource (lib "altium_db") (part "IndStd"))
    )
    (comp (ref "L13")
      (value "600R")
      (footprint "INDC2012X130L")
      (description "600 Ohm, Chip Ferrite Bead")
      (fields
        (field (name "RATING") "200mA")
        (field (name "MANUFACTURER") "Murata")
        (field (name "PARTNUM") "BLM21BD601SN1")
      )
      (libsource (lib "altium_db") (part "IndStd"))
    )
    (comp (ref "L14")
      (value "180R")
      (footprint "INDC1608X130L")
      (description "180 Ohm, Chip Ferrite Brad")
      (fields
        (field (name "RATING") "1500mA")
        (field (name "MANUFACTURER") "Murata")
        (field (name "PARTNUM") "BLM18PG181SN1")
      )
      (libsource (lib "altium_db") (part "IndStd"))
    )
    (comp (ref "L15")
      (value "600R")
      (footprint "INDC2012X130L")
      (description "600 Ohm, Chip Ferrite Bead")
      (fields
        (field (name "RATING") "200mA")
        (field (name "MANUFACTURER") "Murata")
        (field (name "PARTNUM") "BLM21BD601SN1")
      )
      (libsource (lib "altium_db") (part "IndStd"))
    )
    (comp (ref "L16")
      (value "600R")
      (footprint "INDC2012X130L")
      (description "600 Ohm, Chip Ferrite Bead")
      (fields
        (field (name "RATING") "200mA")
        (field (name "MANUFACTURER") "Murata")
        (field (name "PARTNUM") "BLM21BD601SN1")
      )
      (libsource (lib "altium_db") (part "IndStd"))
    )
    (comp (ref "L17")
      (value "600R")
      (footprint "INDC2012X130L")
      (description "600 Ohm, Chip Ferrite Bead")
      (fields
        (field (name "RATING") "200mA")
        (field (name "MANUFACTURER") "Murata")
        (field (name "PARTNUM") "BLM21BD601SN1")
      )
      (libsource (lib "altium_db") (part "IndStd"))
    )
    (comp (ref "U2")
      (value "PPC440EPX-NUA667T")
      (footprint "TE-PBGA680")
      (description "667MHz, non-RoHS, PPC440EPx uProcessor")
      (fields (field (name "MANUFACTURER") "Applied Micro"))
      (libsource (lib "altium_db") (part "PPC440EPX"))
    )
  )
  (nets
    (net (code "1") (name "1V5") (class "Default")
      (node (ref "L11") (pin "1") (pinfunction "1_1") (pintype "passive"))
      (node (ref "L13") (pin "2") (pinfunction "2_2") (pintype "passive"))
      (node (ref "L14") (pin "1") (pinfunction "1_1") (pintype "passive"))
      (node (ref "L17") (pin "1") (pinfunction "1_1") (pintype "passive"))
      (node (ref "L8") (pin "1") (pinfunction "1_1") (pintype "passive"))
    )
    (net (code "2") (name "1V5_PPC") (class "Default")
      (node (ref "C111") (pin "2") (pinfunction "2_2") (pintype "passive"))
      (node (ref "C112") (pin "2") (pinfunction "2_2") (pintype "passive"))
      (node (ref "C113") (pin "2") (pinfunction "2_2") (pintype "passive"))
      (node (ref "C114") (pin "2") (pinfunction "2_2") (pintype "passive"))
      (node (ref "C115") (pin "2") (pinfunction "2_2") (pintype "passive"))
      (node (ref "C116") (pin "2") (pinfunction "2_2") (pintype "passive"))
      (node (ref "C117") (pin "2") (pinfunction "2_2") (pintype "passive"))
      (node (ref "C118") (pin "2") (pinfunction "2_2") (pintype "passive"))
      (node (ref "C119") (pin "2") (pinfunction "2_2") (pintype "passive"))
      (node (ref "C120") (pin "2") (pinfunction "2_2") (pintype "passive"))
      (node (ref "C121") (pin "2") (pinfunction "2_2") (pintype "passive"))
      (node (ref "C122") (pin "2") (pinfunction "2_2") (pintype "passive"))
      (node (ref "C123") (pin "2") (pinfunction "2_2") (pintype "passive"))
      (node (ref "C124") (pin "2") (pinfunction "2_2") (pintype "passive"))
      (node (ref "C125") (pin "2") (pinfunction "2_2") (pintype "passive"))
      (node (ref "C126") (pin "2") (pinfunction "2_2") (pintype "passive"))
      (node (ref "C127") (pin "2") (pinfunction "2_2") (pintype "passive"))
      (node (ref "C128") (pin "2") (pinfunction "2_2") (pintype "passive"))
      (node (ref "C129") (pin "2") (pinfunction "2_2") (pintype "passive"))
      (node (ref "C132") (pin "1") (pinfunction "1_1") (pintype "passive"))
      (node (ref "C133") (pin "1") (pinfunction "1_1") (pintype "passive"))
      (node (ref "C136") (pin "2") (pinfunction "2_2") (pintype "passive"))
      (node (ref "C137") (pin "2") (pinfunction "2_2") (pintype "passive"))
      (node (ref "C138") (pin "2") (pinfunction "2_2") (pintype "passive"))
      (node (ref "C139") (pin "2") (pinfunction "2_2") (pintype "passive"))
      (node (ref "C140") (pin "2") (pinfunction "2_2") (pintype "passive"))
      (node (ref "C141") (pin "2") (pinfunction "2_2") (pintype "passive"))
      (node (ref "C142") (pin "2") (pinfunction "2_2") (pintype "passive"))
      (node (ref "C143") (pin "2") (pinfunction "2_2") (pintype "passive"))
      (node (ref "C144") (pin "2") (pinfunction "2_2") (pintype "passive"))
      (node (ref "C145") (pin "2") (pinfunction "2_2") (pintype "passive"))
      (node (ref "C146") (pin "2") (pinfunction "2_2") (pintype "passive"))
      (node (ref "C147") (pin "2") (pinfunction "2_2") (pintype "passive"))
      (node (ref "C148") (pin "2") (pinfunction "2_2") (pintype "passive"))
      (node (ref "C149") (pin "2") (pinfunction "2_2") (pintype "passive"))
      (node (ref "C150") (pin "2") (pinfunction "2_2") (pintype "passive"))
      (node (ref "C151") (pin "2") (pinfunction "2_2") (pintype "passive"))
      (node (ref "C152") (pin "2") (pinfunction "2_2") (pintype "passive"))
      (node (ref "C153") (pin "2") (pinfunction "2_2") (pintype "passive"))
      (node (ref "C154") (pin "2") (pinfunction "2_2") (pintype "passive"))
      (node (ref "L11") (pin "2") (pinfunction "2_2") (pintype "passive"))
      (node (ref "L14") (pin "2") (pinfunction "2_2") (pintype "passive"))
      (node (ref "L8") (pin "2") (pinfunction "2_2") (pintype "passive"))
      (node (ref "U2") (pin "AA16") (pinfunction "VDD36_AA16") (pintype "input"))
      (node (ref "U2") (pin "AA19") (pinfunction "VDD37_AA19") (pintype "input"))
      (node (ref "U2") (pin "AA30") (pinfunction "VDD38_AA30") (pintype "input"))
      (node (ref "U2") (pin "AA5") (pinfunction "VDD35_AA5") (pintype "input"))
      (node (ref "U2") (pin "AB16") (pinfunction "VDD40_AB16") (pintype "input"))
      (node (ref "U2") (pin "AB19") (pinfunction "VDD41_AB19") (pintype "input"))
      (node (ref "U2") (pin "AB30") (pinfunction "VDD42_AB30") (pintype "input"))
      (node (ref "U2") (pin "AB5") (pinfunction "VDD39_AB5") (pintype "input"))
      (node (ref "U2") (pin "AC30") (pinfunction "VDD44_AC30") (pintype "input"))
      (node (ref "U2") (pin "AC5") (pinfunction "VDD43_AC5") (pintype "input"))
      (node (ref "U2") (pin "AD30") (pinfunction "VDD46_AD30") (pintype "input"))
      (node (ref "U2") (pin "AD5") (pinfunction "VDD45_AD5") (pintype "input"))
      (node (ref "U2") (pin "AK11") (pinfunction "VDD47_AK11") (pintype "input"))
      (node (ref "U2") (pin "AK12") (pinfunction "VDD48_AK12") (pintype "input"))
      (node (ref "U2") (pin "AK13") (pinfunction "VDD49_AK13") (pintype "input"))
      (node (ref "U2") (pin "AK14") (pinfunction "VDD50_AK14") (pintype "input"))
      (node (ref "U2") (pin "AK15") (pinfunction "VDD51_AK15") (pintype "input"))
      (node (ref "U2") (pin "AK20") (pinfunction "VDD52_AK20") (pintype "input"))
      (node (ref "U2") (pin "AK21") (pinfunction "VDD53_AK21") (pintype "input"))
      (node (ref "U2") (pin "AK22") (pinfunction "VDD54_AK22") (pintype "input"))
      (node (ref "U2") (pin "AK23") (pinfunction "VDD55_AK23") (pintype "input"))
      (node (ref "U2") (pin "AK24") (pinfunction "VDD56_AK24") (pintype "input"))
      (node (ref "U2") (pin "E11") (pinfunction "VDD1_E11") (pintype "input"))
      (node (ref "U2") (pin "E12") (pinfunction "VDD2_E12") (pintype "input"))
      (node (ref "U2") (pin "E13") (pinfunction "VDD3_E13") (pintype "input"))
      (node (ref "U2") (pin "E14") (pinfunction "VDD4_E14") (pintype "input"))
      (node (ref "U2") (pin "E15") (pinfunction "VDD5_E15") (pintype "input"))
      (node (ref "U2") (pin "E20") (pinfunction "VDD6_E20") (pintype "input"))
      (node (ref "U2") (pin "E21") (pinfunction "VDD7_E21") (pintype "input"))
      (node (ref "U2") (pin "E22") (pinfunction "VDD8_E22") (pintype "input"))
      (node (ref "U2") (pin "E23") (pinfunction "VDD9_E23") (pintype "input"))
      (node (ref "U2") (pin "E24") (pinfunction "VDD10_E24") (pintype "input"))
      (node (ref "U2") (pin "L30") (pinfunction "VDD12_L30") (pintype "input"))
      (node (ref "U2") (pin "L5") (pinfunction "VDD11_L5") (pintype "input"))
      (node (ref "U2") (pin "M30") (pinfunction "VDD14_M30") (pintype "input"))
      (node (ref "U2") (pin "M5") (pinfunction "VDD13_M5") (pintype "input"))
      (node (ref "U2") (pin "N16") (pinfunction "VDD16_N16") (pintype "input"))
      (node (ref "U2") (pin "N19") (pinfunction "VDD17_N19") (pintype "input"))
      (node (ref "U2") (pin "N30") (pinfunction "VDD18_N30") (pintype "input"))
      (node (ref "U2") (pin "N5") (pinfunction "VDD15_N5") (pintype "input"))
      (node (ref "U2") (pin "P16") (pinfunction "VDD20_P16") (pintype "input"))
      (node (ref "U2") (pin "P19") (pinfunction "VDD21_P19") (pintype "input"))
      (node (ref "U2") (pin "P30") (pinfunction "VDD22_P30") (pintype "input"))
      (node (ref "U2") (pin "P5") (pinfunction "VDD19_P5") (pintype "input"))
      (node (ref "U2") (pin "R30") (pinfunction "VDD24_R30") (pintype "input"))
      (node (ref "U2") (pin "R5") (pinfunction "VDD23_R5") (pintype "input"))
      (node (ref "U2") (pin "T13") (pinfunction "VDD25_T13") (pintype "input"))
      (node (ref "U2") (pin "T14") (pinfunction "VDD26_T14") (pintype "input"))
      (node (ref "U2") (pin "T21") (pinfunction "VDD27_T21") (pintype "input"))
      (node (ref "U2") (pin "T22") (pinfunction "VDD28_T22") (pintype "input"))
      (node (ref "U2") (pin "W13") (pinfunction "VDD29_W13") (pintype "input"))
      (node (ref "U2") (pin "W14") (pinfunction "VDD30_W14") (pintype "input"))
      (node (ref "U2") (pin "W21") (pinfunction "VDD31_W21") (pintype "input"))
      (node (ref "U2") (pin "W22") (pinfunction "VDD32_W22") (pintype "input"))
      (node (ref "U2") (pin "Y30") (pinfunction "VDD34_Y30") (pintype "input"))
      (node (ref "U2") (pin "Y5") (pinfunction "VDD33_Y5") (pintype "input"))
    )
    (net (code "3") (name "1V8") (class "Default")
      (node (ref "L9") (pin "1") (pinfunction "1_1") (pintype "passive"))
    )
    (net (code "4") (name "1V8_PPC") (class "Default")
      (node (ref "C61") (pin "2") (pinfunction "2_2") (pintype "passive"))
      (node (ref "C62") (pin "2") (pinfunction "2_2") (pintype "passive"))
      (node (ref "C63") (pin "2") (pinfunction "2_2") (pintype "passive"))
      (node (ref "C64") (pin "2") (pinfunction "2_2") (pintype "passive"))
      (node (ref "C65") (pin "2") (pinfunction "2_2") (pintype "passive"))
      (node (ref "C66") (pin "2") (pinfunction "2_2") (pintype "passive"))
      (node (ref "C67") (pin "2") (pinfunction "2_2") (pintype "passive"))
      (node (ref "C68") (pin "1") (pinfunction "1_1") (pintype "passive"))
      (node (ref "C69") (pin "1") (pinfunction "1_1") (pintype "passive"))
      (node (ref "C70") (pin "2") (pinfunction "2_2") (pintype "passive"))
      (node (ref "C71") (pin "2") (pinfunction "2_2") (pintype "passive"))
      (node (ref "C72") (pin "2") (pinfunction "2_2") (pintype "passive"))
      (node (ref "C73") (pin "2") (pinfunction "2_2") (pintype "passive"))
      (node (ref "C74") (pin "2") (pinfunction "2_2") (pintype "passive"))
      (node (ref "C75") (pin "2") (pinfunction "2_2") (pintype "passive"))
      (node (ref "C76") (pin "2") (pinfunction "2_2") (pintype "passive"))
      (node (ref "L9") (pin "2") (pinfunction "2_2") (pintype "passive"))
      (node (ref "U2") (pin "AA13") (pinfunction "SOVDD2_AA13") (pintype "input"))
      (node (ref "U2") (pin "AB14") (pinfunction "SOVDD3_AB14") (pintype "input"))
      (node (ref "U2") (pin "AC2") (pinfunction "SOVDD4_AC2") (pintype "input"))
      (node (ref "U2") (pin "AF5") (pinfunction "SOVDD5_AF5") (pintype "input"))
      (node (ref "U2") (pin "AH5") (pinfunction "SOVDD6_AH5") (pintype "input"))
      (node (ref "U2") (pin "AJ5") (pinfunction "SOVDD7_AJ5") (pintype "input"))
      (node (ref "U2") (pin "AK18") (pinfunction "SOVDD12_AK18") (pintype "input"))
      (node (ref "U2") (pin "AK2") (pinfunction "SOVDD8_AK2") (pintype "input"))
      (node (ref "U2") (pin "AK6") (pinfunction "SOVDD9_AK6") (pintype "input"))
      (node (ref "U2") (pin "AK7") (pinfunction "SOVDD10_AK7") (pintype "input"))
      (node (ref "U2") (pin "AK9") (pinfunction "SOVDD11_AK9") (pintype "input"))
      (node (ref "U2") (pin "AN12") (pinfunction "SOVDD14_AN12") (pintype "input"))
      (node (ref "U2") (pin "AN5") (pinfunction "SOVDD13_AN5") (pintype "input"))
      (node (ref "U2") (pin "V5") (pinfunction "SOVDD1_V5") (pintype "input"))
    )
    (net (code "5") (name "2V5") (class "Default")
      (node (ref "L12") (pin "1") (pinfunction "1_1") (pintype "passive"))
    )
    (net (code "6") (name "2V5_PPC") (class "Default")
      (node (ref "C100") (pin "2") (pinfunction "2_2") (pintype "passive"))
      (node (ref "C101") (pin "2") (pinfunction "2_2") (pintype "passive"))
      (node (ref "C85") (pin "2") (pinfunction "2_2") (pintype "passive"))
      (node (ref "C86") (pin "2") (pinfunction "2_2") (pintype "passive"))
      (node (ref "C87") (pin "2") (pinfunction "2_2") (pintype "passive"))
      (node (ref "C88") (pin "2") (pinfunction "2_2") (pintype "passive"))
      (node (ref "C89") (pin "2") (pinfunction "2_2") (pintype "passive"))
      (node (ref "C90") (pin "2") (pinfunction "2_2") (pintype "passive"))
      (node (ref "C94") (pin "1") (pinfunction "1_1") (pintype "passive"))
      (node (ref "C95") (pin "1") (pinfunction "1_1") (pintype "passive"))
      (node (ref "C96") (pin "2") (pinfunction "2_2") (pintype "passive"))
      (node (ref "C97") (pin "2") (pinfunction "2_2") (pintype "passive"))
      (node (ref "C98") (pin "2") (pinfunction "2_2") (pintype "passive"))
      (node (ref "C99") (pin "2") (pinfunction "2_2") (pintype "passive"))
      (node (ref "L12") (pin "2") (pinfunction "2_2") (pintype "passive"))
      (node (ref "U2") (pin "AA22") (pinfunction "EOVDD1_AA22") (pintype "input"))
      (node (ref "U2") (pin "AB21") (pinfunction "EOVDD2_AB21") (pintype "input"))
      (node (ref "U2") (pin "AC33") (pinfunction "EOVDD3_AC33") (pintype "input"))
      (node (ref "U2") (pin "AF30") (pinfunction "EOVDD4_AF30") (pintype "input"))
      (node (ref "U2") (pin "AH30") (pinfunction "EOVDD5_AH30") (pintype "input"))
      (node (ref "U2") (pin "AJ30") (pinfunction "EOVDD6_AJ30") (pintype "input"))
      (node (ref "U2") (pin "AK26") (pinfunction "EOVDD7_AK26") (pintype "input"))
      (node (ref "U2") (pin "AK28") (pinfunction "EOVDD8_AK28") (pintype "input"))
      (node (ref "U2") (pin "AK29") (pinfunction "EOVDD9_AK29") (pintype "input"))
      (node (ref "U2") (pin "AK33") (pinfunction "EOVDD10_AK33") (pintype "input"))
      (node (ref "U2") (pin "AN23") (pinfunction "EOVDD11_AN23") (pintype "input"))
      (node (ref "U2") (pin "AN30") (pinfunction "EOVDD12_AN30") (pintype "input"))
    )
    (net (code "7") (name "3V3") (class "Default")
      (node (ref "L10") (pin "1") (pinfunction "1_1") (pintype "passive"))
      (node (ref "L15") (pin "1") (pinfunction "1_1") (pintype "passive"))
      (node (ref "L16") (pin "2") (pinfunction "2_2") (pintype "passive"))
    )
    (net (code "8") (name "3V3_PPC") (class "Default")
      (node (ref "C102") (pin "2") (pinfunction "2_2") (pintype "passive"))
      (node (ref "C103") (pin "2") (pinfunction "2_2") (pintype "passive"))
      (node (ref "C104") (pin "2") (pinfunction "2_2") (pintype "passive"))
      (node (ref "C105") (pin "2") (pinfunction "2_2") (pintype "passive"))
      (node (ref "C106") (pin "2") (pinfunction "2_2") (pintype "passive"))
      (node (ref "C107") (pin "2") (pinfunction "2_2") (pintype "passive"))
      (node (ref "C108") (pin "2") (pinfunction "2_2") (pintype "passive"))
      (node (ref "C109") (pin "2") (pinfunction "2_2") (pintype "passive"))
      (node (ref "C110") (pin "2") (pinfunction "2_2") (pintype "passive"))
      (node (ref "C130") (pin "1") (pinfunction "1_1") (pintype "passive"))
      (node (ref "C131") (pin "1") (pinfunction "1_1") (pintype "passive"))
      (node (ref "C134") (pin "2") (pinfunction "2_2") (pintype "passive"))
      (node (ref "C135") (pin "2") (pinfunction "2_2") (pintype "passive"))
      (node (ref "C155") (pin "2") (pinfunction "2_2") (pintype "passive"))
      (node (ref "C156") (pin "2") (pinfunction "2_2") (pintype "passive"))
      (node (ref "C157") (pin "2") (pinfunction "2_2") (pintype "passive"))
      (node (ref "C158") (pin "2") (pinfunction "2_2") (pintype "passive"))
      (node (ref "C159") (pin "2") (pinfunction "2_2") (pintype "passive"))
      (node (ref "C160") (pin "2") (pinfunction "2_2") (pintype "passive"))
      (node (ref "C161") (pin "2") (pinfunction "2_2") (pintype "passive"))
      (node (ref "L10") (pin "2") (pinfunction "2_2") (pintype "passive"))
      (node (ref "U2") (pin "B12") (pinfunction "OVDD2_B12") (pintype "input"))
      (node (ref "U2") (pin "B23") (pinfunction "OVDD3_B23") (pintype "input"))
      (node (ref "U2") (pin "B30") (pinfunction "OVDD4_B30") (pintype "input"))
      (node (ref "U2") (pin "B5") (pinfunction "OVDD1_B5") (pintype "input"))
      (node (ref "U2") (pin "E17") (pinfunction "OVDD9_E17") (pintype "input"))
      (node (ref "U2") (pin "E2") (pinfunction "OVDD5_E2") (pintype "input"))
      (node (ref "U2") (pin "E26") (pinfunction "OVDD10_E26") (pintype "input"))
      (node (ref "U2") (pin "E28") (pinfunction "OVDD11_E28") (pintype "input"))
      (node (ref "U2") (pin "E29") (pinfunction "OVDD12_E29") (pintype "input"))
      (node (ref "U2") (pin "E33") (pinfunction "OVDD13_E33") (pintype "input"))
      (node (ref "U2") (pin "E6") (pinfunction "OVDD6_E6") (pintype "input"))
      (node (ref "U2") (pin "E7") (pinfunction "OVDD7_E7") (pintype "input"))
      (node (ref "U2") (pin "E9") (pinfunction "OVDD8_E9") (pintype "input"))
      (node (ref "U2") (pin "F30") (pinfunction "OVDD15_F30") (pintype "input"))
      (node (ref "U2") (pin "F5") (pinfunction "OVDD14_F5") (pintype "input"))
      (node (ref "U2") (pin "G30") (pinfunction "OVDD17_G30") (pintype "input"))
      (node (ref "U2") (pin "G5") (pinfunction "OVDD16_G5") (pintype "input"))
      (node (ref "U2") (pin "J30") (pinfunction "OVDD19_J30") (pintype "input"))
      (node (ref "U2") (pin "J5") (pinfunction "OVDD18_J5") (pintype "input"))
      (node (ref "U2") (pin "M2") (pinfunction "OVDD20_M2") (pintype "input"))
      (node (ref "U2") (pin "M33") (pinfunction "OVDD21_M33") (pintype "input"))
      (node (ref "U2") (pin "N14") (pinfunction "OVDD22_N14") (pintype "input"))
      (node (ref "U2") (pin "N21") (pinfunction "OVDD23_N21") (pintype "input"))
      (node (ref "U2") (pin "P13") (pinfunction "OVDD24_P13") (pintype "input"))
      (node (ref "U2") (pin "P22") (pinfunction "OVDD25_P22") (pintype "input"))
      (node (ref "U2") (pin "U30") (pinfunction "OVDD26_U30") (pintype "input"))
    )
    (net (code "9") (name "GND") (class "Default")
      (node (ref "C100") (pin "1") (pinfunction "1_1") (pintype "passive"))
      (node (ref "C101") (pin "1") (pinfunction "1_1") (pintype "passive"))
      (node (ref "C102") (pin "1") (pinfunction "1_1") (pintype "passive"))
      (node (ref "C103") (pin "1") (pinfunction "1_1") (pintype "passive"))
      (node (ref "C104") (pin "1") (pinfunction "1_1") (pintype "passive"))
      (node (ref "C105") (pin "1") (pinfunction "1_1") (pintype "passive"))
      (node (ref "C106") (pin "1") (pinfunction "1_1") (pintype "passive"))
      (node (ref "C107") (pin "1") (pinfunction "1_1") (pintype "passive"))
      (node (ref "C108") (pin "1") (pinfunction "1_1") (pintype "passive"))
      (node (ref "C109") (pin "1") (pinfunction "1_1") (pintype "passive"))
      (node (ref "C110") (pin "1") (pinfunction "1_1") (pintype "passive"))
      (node (ref "C111") (pin "1") (pinfunction "1_1") (pintype "passive"))
      (node (ref "C112") (pin "1") (pinfunction "1_1") (pintype "passive"))
      (node (ref "C113") (pin "1") (pinfunction "1_1") (pintype "passive"))
      (node (ref "C114") (pin "1") (pinfunction "1_1") (pintype "passive"))
      (node (ref "C115") (pin "1") (pinfunction "1_1") (pintype "passive"))
      (node (ref "C116") (pin "1") (pinfunction "1_1") (pintype "passive"))
      (node (ref "C117") (pin "1") (pinfunction "1_1") (pintype "passive"))
      (node (ref "C118") (pin "1") (pinfunction "1_1") (pintype "passive"))
      (node (ref "C119") (pin "1") (pinfunction "1_1") (pintype "passive"))
      (node (ref "C120") (pin "1") (pinfunction "1_1") (pintype "passive"))
      (node (ref "C121") (pin "1") (pinfunction "1_1") (pintype "passive"))
      (node (ref "C122") (pin "1") (pinfunction "1_1") (pintype "passive"))
      (node (ref "C123") (pin "1") (pinfunction "1_1") (pintype "passive"))
      (node (ref "C124") (pin "1") (pinfunction "1_1") (pintype "passive"))
      (node (ref "C125") (pin "1") (pinfunction "1_1") (pintype "passive"))
      (node (ref "C126") (pin "1") (pinfunction "1_1") (pintype "passive"))
      (node (ref "C127") (pin "1") (pinfunction "1_1") (pintype "passive"))
      (node (ref "C128") (pin "1") (pinfunction "1_1") (pintype "passive"))
      (node (ref "C129") (pin "1") (pinfunction "1_1") (pintype "passive"))
      (node (ref "C130") (pin "2") (pinfunction "2_2") (pintype "passive"))
      (node (ref "C131") (pin "2") (pinfunction "2_2") (pintype "passive"))
      (node (ref "C132") (pin "2") (pinfunction "2_2") (pintype "passive"))
      (node (ref "C133") (pin "2") (pinfunction "2_2") (pintype "passive"))
      (node (ref "C134") (pin "1") (pinfunction "1_1") (pintype "passive"))
      (node (ref "C135") (pin "1") (pinfunction "1_1") (pintype "passive"))
      (node (ref "C136") (pin "1") (pinfunction "1_1") (pintype "passive"))
      (node (ref "C137") (pin "1") (pinfunction "1_1") (pintype "passive"))
      (node (ref "C138") (pin "1") (pinfunction "1_1") (pintype "passive"))
      (node (ref "C139") (pin "1") (pinfunction "1_1") (pintype "passive"))
      (node (ref "C140") (pin "1") (pinfunction "1_1") (pintype "passive"))
      (node (ref "C141") (pin "1") (pinfunction "1_1") (pintype "passive"))
      (node (ref "C142") (pin "1") (pinfunction "1_1") (pintype "passive"))
      (node (ref "C143") (pin "1") (pinfunction "1_1") (pintype "passive"))
      (node (ref "C144") (pin "1") (pinfunction "1_1") (pintype "passive"))
      (node (ref "C145") (pin "1") (pinfunction "1_1") (pintype "passive"))
      (node (ref "C146") (pin "1") (pinfunction "1_1") (pintype "passive"))
      (node (ref "C147") (pin "1") (pinfunction "1_1") (pintype "passive"))
      (node (ref "C148") (pin "1") (pinfunction "1_1") (pintype "passive"))
      (node (ref "C149") (pin "1") (pinfunction "1_1") (pintype "passive"))
      (node (ref "C150") (pin "1") (pinfunction "1_1") (pintype "passive"))
      (node (ref "C151") (pin "1") (pinfunction "1_1") (pintype "passive"))
      (node (ref "C152") (pin "1") (pinfunction "1_1") (pintype "passive"))
      (node (ref "C153") (pin "1") (pinfunction "1_1") (pintype "passive"))
      (node (ref "C154") (pin "1") (pinfunction "1_1") (pintype "passive"))
      (node (ref "C155") (pin "1") (pinfunction "1_1") (pintype "passive"))
      (node (ref "C156") (pin "1") (pinfunction "1_1") (pintype "passive"))
      (node (ref "C157") (pin "1") (pinfunction "1_1") (pintype "passive"))
      (node (ref "C158") (pin "1") (pinfunction "1_1") (pintype "passive"))
      (node (ref "C159") (pin "1") (pinfunction "1_1") (pintype "passive"))
      (node (ref "C160") (pin "1") (pinfunction "1_1") (pintype "passive"))
      (node (ref "C161") (pin "1") (pinfunction "1_1") (pintype "passive"))
      (node (ref "C58") (pin "1") (pinfunction "1_1") (pintype "passive"))
      (node (ref "C59") (pin "1") (pinfunction "1_1") (pintype "passive"))
      (node (ref "C60") (pin "1") (pinfunction "1_1") (pintype "passive"))
      (node (ref "C61") (pin "1") (pinfunction "1_1") (pintype "passive"))
      (node (ref "C62") (pin "1") (pinfunction "1_1") (pintype "passive"))
      (node (ref "C63") (pin "1") (pinfunction "1_1") (pintype "passive"))
      (node (ref "C64") (pin "1") (pinfunction "1_1") (pintype "passive"))
      (node (ref "C65") (pin "1") (pinfunction "1_1") (pintype "passive"))
      (node (ref "C66") (pin "1") (pinfunction "1_1") (pintype "passive"))
      (node (ref "C67") (pin "1") (pinfunction "1_1") (pintype "passive"))
      (node (ref "C68") (pin "2") (pinfunction "2_2") (pintype "passive"))
      (node (ref "C69") (pin "2") (pinfunction "2_2") (pintype "passive"))
      (node (ref "C70") (pin "1") (pinfunction "1_1") (pintype "passive"))
      (node (ref "C71") (pin "1") (pinfunction "1_1") (pintype "passive"))
      (node (ref "C72") (pin "1") (pinfunction "1_1") (pintype "passive"))
      (node (ref "C73") (pin "1") (pinfunction "1_1") (pintype "passive"))
      (node (ref "C74") (pin "1") (pinfunction "1_1") (pintype "passive"))
      (node (ref "C75") (pin "1") (pinfunction "1_1") (pintype "passive"))
      (node (ref "C76") (pin "1") (pinfunction "1_1") (pintype "passive"))
      (node (ref "C77") (pin "1") (pinfunction "1_1") (pintype "passive"))
      (node (ref "C78") (pin "1") (pinfunction "1_1") (pintype "passive"))
      (node (ref "C79") (pin "1") (pinfunction "1_1") (pintype "passive"))
      (node (ref "C80") (pin "1") (pinfunction "1_1") (pintype "passive"))
      (node (ref "C81") (pin "1") (pinfunction "1_1") (pintype "passive"))
      (node (ref "C82") (pin "1") (pinfunction "1_1") (pintype "passive"))
      (node (ref "C83") (pin "1") (pinfunction "1_1") (pintype "passive"))
      (node (ref "C84") (pin "1") (pinfunction "1_1") (pintype "passive"))
      (node (ref "C85") (pin "1") (pinfunction "1_1") (pintype "passive"))
      (node (ref "C86") (pin "1") (pinfunction "1_1") (pintype "passive"))
      (node (ref "C87") (pin "1") (pinfunction "1_1") (pintype "passive"))
      (node (ref "C88") (pin "1") (pinfunction "1_1") (pintype "passive"))
      (node (ref "C89") (pin "1") (pinfunction "1_1") (pintype "passive"))
      (node (ref "C90") (pin "1") (pinfunction "1_1") (pintype "passive"))
      (node (ref "C91") (pin "1") (pinfunction "1_1") (pintype "passive"))
      (node (ref "C92") (pin "1") (pinfunction "1_1") (pintype "passive"))
      (node (ref "C93") (pin "1") (pinfunction "1_1") (pintype "passive"))
      (node (ref "C94") (pin "2") (pinfunction "2_2") (pintype "passive"))
      (node (ref "C95") (pin "2") (pinfunction "2_2") (pintype "passive"))
      (node (ref "C96") (pin "1") (pinfunction "1_1") (pintype "passive"))
      (node (ref "C97") (pin "1") (pinfunction "1_1") (pintype "passive"))
      (node (ref "C98") (pin "1") (pinfunction "1_1") (pintype "passive"))
      (node (ref "C99") (pin "1") (pinfunction "1_1") (pintype "passive"))
      (node (ref "U2") (pin "A1") (pinfunction "GND1_A1") (pintype "input"))
      (node (ref "U2") (pin "A2") (pinfunction "GND2_A2") (pintype "input"))
      (node (ref "U2") (pin "A28") (pinfunction "GND4_A28") (pintype "input"))
      (node (ref "U2") (pin "A3") (pinfunction "GND3_A3") (pintype "input"))
      (node (ref "U2") (pin "A32") (pinfunction "GND5_A32") (pintype "input"))
      (node (ref "U2") (pin "A33") (pinfunction "GND6_A33") (pintype "input"))
      (node (ref "U2") (pin "A34") (pinfunction "GND7_A34") (pintype "input"))
      (node (ref "U2") (pin "AA14") (pinfunction "GND128_AA14") (pintype "input"))
      (node (ref "U2") (pin "AA15") (pinfunction "GND129_AA15") (pintype "input"))
      (node (ref "U2") (pin "AA17") (pinfunction "GND130_AA17") (pintype "input"))
      (node (ref "U2") (pin "AA18") (pinfunction "GND131_AA18") (pintype "input"))
      (node (ref "U2") (pin "AA20") (pinfunction "GND132_AA20") (pintype "input"))
      (node (ref "U2") (pin "AA21") (pinfunction "GND133_AA21") (pintype "input"))
      (node (ref "U2") (pin "AB13") (pinfunction "GND134_AB13") (pintype "input"))
      (node (ref "U2") (pin "AB15") (pinfunction "GND135_AB15") (pintype "input"))
      (node (ref "U2") (pin "AB17") (pinfunction "GND136_AB17") (pintype "input"))
      (node (ref "U2") (pin "AB18") (pinfunction "GND137_AB18") (pintype "input"))
      (node (ref "U2") (pin "AB20") (pinfunction "GND138_AB20") (pintype "input"))
      (node (ref "U2") (pin "AB22") (pinfunction "GND139_AB22") (pintype "input"))
      (node (ref "U2") (pin "AD1") (pinfunction "GND140_AD1") (pintype "input"))
      (node (ref "U2") (pin "AE30") (pinfunction "GND142_AE30") (pintype "input"))
      (node (ref "U2") (pin "AE5") (pinfunction "GND141_AE5") (pintype "input"))
      (node (ref "U2") (pin "AG2") (pinfunction "GND143_AG2") (pintype "input"))
      (node (ref "U2") (pin "AG30") (pinfunction "GND145_AG30") (pintype "input"))
      (node (ref "U2") (pin "AG33") (pinfunction "GND146_AG33") (pintype "input"))
      (node (ref "U2") (pin "AG5") (pinfunction "GND144_AG5") (pintype "input"))
      (node (ref "U2") (pin "AJ1") (pinfunction "GND147_AJ1") (pintype "input"))
      (node (ref "U2") (pin "AK10") (pinfunction "GND151_AK10") (pintype "input"))
      (node (ref "U2") (pin "AK16") (pinfunction "GND152_AK16") (pintype "input"))
      (node (ref "U2") (pin "AK17") (pinfunction "GND153_AK17") (pintype "input"))
      (node (ref "U2") (pin "AK19") (pinfunction "GND154_AK19") (pintype "input"))
      (node (ref "U2") (pin "AK25") (pinfunction "GND155_AK25") (pintype "input"))
      (node (ref "U2") (pin "AK27") (pinfunction "GND156_AK27") (pintype "input"))
      (node (ref "U2") (pin "AK30") (pinfunction "GND157_AK30") (pintype "input"))
      (node (ref "U2") (pin "AK31") (pinfunction "GND158_AK31") (pintype "input"))
      (node (ref "U2") (pin "AK4") (pinfunction "GND148_AK4") (pintype "input"))
      (node (ref "U2") (pin "AK5") (pinfunction "GND149_AK5") (pintype "input"))
      (node (ref "U2") (pin "AK8") (pinfunction "GND150_AK8") (pintype "input"))
      (node (ref "U2") (pin "AL29") (pinfunction "GND163_AL29") (pintype "input"))
      (node (ref "U2") (pin "AL3") (pinfunction "GND159_AL3") (pintype "input"))
      (node (ref "U2") (pin "AL30") (pinfunction "GND164_AL30") (pintype "input"))
      (node (ref "U2") (pin "AL31") (pinfunction "GND165_AL31") (pintype "input"))
      (node (ref "U2") (pin "AL32") (pinfunction "GND166_AL32") (pintype "input"))
      (node (ref "U2") (pin "AL4") (pinfunction "GND160_AL4") (pintype "input"))
      (node (ref "U2") (pin "AL5") (pinfunction "GND161_AL5") (pintype "input"))
      (node (ref "U2") (pin "AL6") (pinfunction "GND162_AL6") (pintype "input"))
      (node (ref "U2") (pin "AM1") (pinfunction "GND167_AM1") (pintype "input"))
      (node (ref "U2") (pin "AM2") (pinfunction "GND168_AM2") (pintype "input"))
      (node (ref "U2") (pin "AM3") (pinfunction "GND169_AM3") (pintype "input"))
      (node (ref "U2") (pin "AM31") (pinfunction "GND171_AM31") (pintype "input"))
      (node (ref "U2") (pin "AM32") (pinfunction "GND172_AM32") (pintype "input"))
      (node (ref "U2") (pin "AM33") (pinfunction "GND173_AM33") (pintype "input"))
      (node (ref "U2") (pin "AM34") (pinfunction "GND174_AM34") (pintype "input"))
      (node (ref "U2") (pin "AM4") (pinfunction "GND170_AM4") (pintype "input"))
      (node (ref "U2") (pin "AN1") (pinfunction "GND175_AN1") (pintype "input"))
      (node (ref "U2") (pin "AN16") (pinfunction "GND180_AN16") (pintype "input"))
      (node (ref "U2") (pin "AN19") (pinfunction "GND181_AN19") (pintype "input"))
      (node (ref "U2") (pin "AN2") (pinfunction "GND176_AN2") (pintype "input"))
      (node (ref "U2") (pin "AN27") (pinfunction "GND182_AN27") (pintype "input"))
      (node (ref "U2") (pin "AN3") (pinfunction "GND177_AN3") (pintype "input"))
      (node (ref "U2") (pin "AN31") (pinfunction "GND183_AN31") (pintype "input"))
      (node (ref "U2") (pin "AN32") (pinfunction "GND184_AN32") (pintype "input"))
      (node (ref "U2") (pin "AN33") (pinfunction "GND185_AN33") (pintype "input"))
      (node (ref "U2") (pin "AN34") (pinfunction "GND186_AN34") (pintype "input"))
      (node (ref "U2") (pin "AN4") (pinfunction "GND178_AN4") (pintype "input"))
      (node (ref "U2") (pin "AN8") (pinfunction "GND179_AN8") (pintype "input"))
      (node (ref "U2") (pin "AP1") (pinfunction "GND187_AP1") (pintype "input"))
      (node (ref "U2") (pin "AP2") (pinfunction "GND188_AP2") (pintype "input"))
      (node (ref "U2") (pin "AP25") (pinfunction "AGND_AP25") (pintype "input"))
      (node (ref "U2") (pin "AP27") (pinfunction "EAGND_AP27") (pintype "input"))
      (node (ref "U2") (pin "AP3") (pinfunction "GND189_AP3") (pintype "input"))
      (node (ref "U2") (pin "AP32") (pinfunction "GND190_AP32") (pintype "input"))
      (node (ref "U2") (pin "AP33") (pinfunction "GND191_AP33") (pintype "input"))
      (node (ref "U2") (pin "AP34") (pinfunction "GND192_AP34") (pintype "input"))
      (node (ref "U2") (pin "B1") (pinfunction "GND8_B1") (pintype "input"))
      (node (ref "U2") (pin "B16") (pinfunction "GND13_B16") (pintype "input"))
      (node (ref "U2") (pin "B19") (pinfunction "GND14_B19") (pintype "input"))
      (node (ref "U2") (pin "B2") (pinfunction "GND9_B2") (pintype "input"))
      (node (ref "U2") (pin "B26") (pinfunction "GND15_B26") (pintype "input"))
      (node (ref "U2") (pin "B27") (pinfunction "GND16_B27") (pintype "input"))
      (node (ref "U2") (pin "B3") (pinfunction "GND10_B3") (pintype "input"))
      (node (ref "U2") (pin "B31") (pinfunction "GND17_B31") (pintype "input"))
      (node (ref "U2") (pin "B32") (pinfunction "GND18_B32") (pintype "input"))
      (node (ref "U2") (pin "B33") (pinfunction "GND19_B33") (pintype "input"))
      (node (ref "U2") (pin "B34") (pinfunction "GND20_B34") (pintype "input"))
      (node (ref "U2") (pin "B4") (pinfunction "GND11_B4") (pintype "input"))
      (node (ref "U2") (pin "B8") (pinfunction "GND12_B8") (pintype "input"))
      (node (ref "U2") (pin "C2") (pinfunction "GND21_C2") (pintype "input"))
      (node (ref "U2") (pin "C3") (pinfunction "GND22_C3") (pintype "input"))
      (node (ref "U2") (pin "C31") (pinfunction "GND24_C31") (pintype "input"))
      (node (ref "U2") (pin "C32") (pinfunction "GND25_C32") (pintype "input"))
      (node (ref "U2") (pin "C33") (pinfunction "GND26_C33") (pintype "input"))
      (node (ref "U2") (pin "C34") (pinfunction "GND27_C34") (pintype "input"))
      (node (ref "U2") (pin "C4") (pinfunction "GND23_C4") (pintype "input"))
      (node (ref "U2") (pin "D3") (pinfunction "GND28_D3") (pintype "input"))
      (node (ref "U2") (pin "D30") (pinfunction "GND31_D30") (pintype "input"))
      (node (ref "U2") (pin "D31") (pinfunction "GND32_D31") (pintype "input"))
      (node (ref "U2") (pin "D32") (pinfunction "GND33_D32") (pintype "input"))
      (node (ref "U2") (pin "D33") (pinfunction "GND34_D33") (pintype "input"))
      (node (ref "U2") (pin "D4") (pinfunction "GND29_D4") (pintype "input"))
      (node (ref "U2") (pin "D5") (pinfunction "GND30_D5") (pintype "input"))
      (node (ref "U2") (pin "E10") (pinfunction "GND37_E10") (pintype "input"))
      (node (ref "U2") (pin "E16") (pinfunction "GND38_E16") (pintype "input"))
      (node (ref "U2") (pin "E18") (pinfunction "GND39_E18") (pintype "input"))
      (node (ref "U2") (pin "E19") (pinfunction "GND40_E19") (pintype "input"))
      (node (ref "U2") (pin "E25") (pinfunction "GND41_E25") (pintype "input"))
      (node (ref "U2") (pin "E27") (pinfunction "GND42_E27") (pintype "input"))
      (node (ref "U2") (pin "E30") (pinfunction "GND43_E30") (pintype "input"))
      (node (ref "U2") (pin "E31") (pinfunction "GND44_E31") (pintype "input"))
      (node (ref "U2") (pin "E5") (pinfunction "GND35_E5") (pintype "input"))
      (node (ref "U2") (pin "E8") (pinfunction "GND36_E8") (pintype "input"))
      (node (ref "U2") (pin "H1") (pinfunction "GND45_H1") (pintype "input"))
      (node (ref "U2") (pin "H2") (pinfunction "GND46_H2") (pintype "input"))
      (node (ref "U2") (pin "H30") (pinfunction "GND48_H30") (pintype "input"))
      (node (ref "U2") (pin "H33") (pinfunction "GND49_H33") (pintype "input"))
      (node (ref "U2") (pin "H5") (pinfunction "GND47_H5") (pintype "input"))
      (node (ref "U2") (pin "J3") (pinfunction "UAGND3_J3") (pintype "input"))
      (node (ref "U2") (pin "K1") (pinfunction "UAGND5_K1") (pintype "input"))
      (node (ref "U2") (pin "K30") (pinfunction "GND51_K30") (pintype "input"))
      (node (ref "U2") (pin "K4") (pinfunction "UAGND4_K4") (pintype "input"))
      (node (ref "U2") (pin "K5") (pinfunction "GND50_K5") (pintype "input"))
      (node (ref "U2") (pin "M1") (pinfunction "UAGND2_M1") (pintype "input"))
      (node (ref "U2") (pin "M4") (pinfunction "UAGND1_M4") (pintype "input"))
      (node (ref "U2") (pin "N1") (pinfunction "GND52_N1") (pintype "input"))
      (node (ref "U2") (pin "N13") (pinfunction "GND54_N13") (pintype "input"))
      (node (ref "U2") (pin "N15") (pinfunction "GND55_N15") (pintype "input"))
      (node (ref "U2") (pin "N17") (pinfunction "GND56_N17") (pintype "input"))
      (node (ref "U2") (pin "N18") (pinfunction "GND57_N18") (pintype "input"))
      (node (ref "U2") (pin "N20") (pinfunction "GND58_N20") (pintype "input"))
      (node (ref "U2") (pin "N22") (pinfunction "GND59_N22") (pintype "input"))
      (node (ref "U2") (pin "N4") (pinfunction "GND53_N4") (pintype "input"))
      (node (ref "U2") (pin "P14") (pinfunction "GND60_P14") (pintype "input"))
      (node (ref "U2") (pin "P15") (pinfunction "GND61_P15") (pintype "input"))
      (node (ref "U2") (pin "P17") (pinfunction "GND62_P17") (pintype "input"))
      (node (ref "U2") (pin "P18") (pinfunction "GND63_P18") (pintype "input"))
      (node (ref "U2") (pin "P20") (pinfunction "GND64_P20") (pintype "input"))
      (node (ref "U2") (pin "P21") (pinfunction "GND65_P21") (pintype "input"))
      (node (ref "U2") (pin "R13") (pinfunction "GND66_R13") (pintype "input"))
      (node (ref "U2") (pin "R14") (pinfunction "GND67_R14") (pintype "input"))
      (node (ref "U2") (pin "R15") (pinfunction "GND68_R15") (pintype "input"))
      (node (ref "U2") (pin "R16") (pinfunction "GND69_R16") (pintype "input"))
      (node (ref "U2") (pin "R17") (pinfunction "GND70_R17") (pintype "input"))
      (node (ref "U2") (pin "R18") (pinfunction "GND71_R18") (pintype "input"))
      (node (ref "U2") (pin "R19") (pinfunction "GND72_R19") (pintype "input"))
      (node (ref "U2") (pin "R20") (pinfunction "GND73_R20") (pintype "input"))
      (node (ref "U2") (pin "R21") (pinfunction "GND74_R21") (pintype "input"))
      (node (ref "U2") (pin "R22") (pinfunction "GND75_R22") (pintype "input"))
      (node (ref "U2") (pin "T15") (pinfunction "GND78_T15") (pintype "input"))
      (node (ref "U2") (pin "T16") (pinfunction "GND79_T16") (pintype "input"))
      (node (ref "U2") (pin "T17") (pinfunction "GND80_T17") (pintype "input"))
      (node (ref "U2") (pin "T18") (pinfunction "GND81_T18") (pintype "input"))
      (node (ref "U2") (pin "T19") (pinfunction "GND82_T19") (pintype "input"))
      (node (ref "U2") (pin "T2") (pinfunction "GND76_T2") (pintype "input"))
      (node (ref "U2") (pin "T20") (pinfunction "GND83_T20") (pintype "input"))
      (node (ref "U2") (pin "T30") (pinfunction "GND84_T30") (pintype "input"))
      (node (ref "U2") (pin "T33") (pinfunction "GND85_T33") (pintype "input"))
      (node (ref "U2") (pin "T5") (pinfunction "GND77_T5") (pintype "input"))
      (node (ref "U2") (pin "U13") (pinfunction "GND87_U13") (pintype "input"))
      (node (ref "U2") (pin "U14") (pinfunction "GND88_U14") (pintype "input"))
      (node (ref "U2") (pin "U15") (pinfunction "GND89_U15") (pintype "input"))
      (node (ref "U2") (pin "U16") (pinfunction "GND90_U16") (pintype "input"))
      (node (ref "U2") (pin "U17") (pinfunction "GND91_U17") (pintype "input"))
      (node (ref "U2") (pin "U18") (pinfunction "GND92_U18") (pintype "input"))
      (node (ref "U2") (pin "U19") (pinfunction "GND93_U19") (pintype "input"))
      (node (ref "U2") (pin "U20") (pinfunction "GND94_U20") (pintype "input"))
      (node (ref "U2") (pin "U21") (pinfunction "GND95_U21") (pintype "input"))
      (node (ref "U2") (pin "U22") (pinfunction "GND96_U22") (pintype "input"))
      (node (ref "U2") (pin "U5") (pinfunction "GND86_U5") (pintype "input"))
      (node (ref "U2") (pin "V13") (pinfunction "GND97_V13") (pintype "input"))
      (node (ref "U2") (pin "V14") (pinfunction "GND98_V14") (pintype "input"))
      (node (ref "U2") (pin "V15") (pinfunction "GND99_V15") (pintype "input"))
      (node (ref "U2") (pin "V16") (pinfunction "GND100_V16") (pintype "input"))
      (node (ref "U2") (pin "V17") (pinfunction "GND101_V17") (pintype "input"))
      (node (ref "U2") (pin "V18") (pinfunction "GND102_V18") (pintype "input"))
      (node (ref "U2") (pin "V19") (pinfunction "GND103_V19") (pintype "input"))
      (node (ref "U2") (pin "V20") (pinfunction "GND104_V20") (pintype "input"))
      (node (ref "U2") (pin "V21") (pinfunction "GND105_V21") (pintype "input"))
      (node (ref "U2") (pin "V22") (pinfunction "GND106_V22") (pintype "input"))
      (node (ref "U2") (pin "V30") (pinfunction "GND107_V30") (pintype "input"))
      (node (ref "U2") (pin "W15") (pinfunction "GND110_W15") (pintype "input"))
      (node (ref "U2") (pin "W16") (pinfunction "GND111_W16") (pintype "input"))
      (node (ref "U2") (pin "W17") (pinfunction "GND112_W17") (pintype "input"))
      (node (ref "U2") (pin "W18") (pinfunction "GND113_W18") (pintype "input"))
      (node (ref "U2") (pin "W19") (pinfunction "GND114_W19") (pintype "input"))
      (node (ref "U2") (pin "W2") (pinfunction "GND108_W2") (pintype "input"))
      (node (ref "U2") (pin "W20") (pinfunction "GND115_W20") (pintype "input"))
      (node (ref "U2") (pin "W30") (pinfunction "GND116_W30") (pintype "input"))
      (node (ref "U2") (pin "W33") (pinfunction "GND117_W33") (pintype "input"))
      (node (ref "U2") (pin "W5") (pinfunction "GND109_W5") (pintype "input"))
      (node (ref "U2") (pin "Y13") (pinfunction "GND118_Y13") (pintype "input"))
      (node (ref "U2") (pin "Y14") (pinfunction "GND119_Y14") (pintype "input"))
      (node (ref "U2") (pin "Y15") (pinfunction "GND120_Y15") (pintype "input"))
      (node (ref "U2") (pin "Y16") (pinfunction "GND121_Y16") (pintype "input"))
      (node (ref "U2") (pin "Y17") (pinfunction "GND122_Y17") (pintype "input"))
      (node (ref "U2") (pin "Y18") (pinfunction "GND123_Y18") (pintype "input"))
      (node (ref "U2") (pin "Y19") (pinfunction "GND124_Y19") (pintype "input"))
      (node (ref "U2") (pin "Y20") (pinfunction "GND125_Y20") (pintype "input"))
      (node (ref "U2") (pin "Y21") (pinfunction "GND126_Y21") (pintype "input"))
      (node (ref "U2") (pin "Y22") (pinfunction "GND127_Y22") (pintype "input"))
    )
    (net (code "10") (name "Net-(U2J-AVDD)") (class "Default")
      (node (ref "C58") (pin "2") (pinfunction "2_2") (pintype "passive"))
      (node (ref "C59") (pin "2") (pinfunction "2_2") (pintype "passive"))
      (node (ref "C60") (pin "2") (pinfunction "2_2") (pintype "passive"))
      (node (ref "L13") (pin "1") (pinfunction "1_1") (pintype "passive"))
      (node (ref "U2") (pin "AP24") (pinfunction "AVDD_AP24") (pintype "input"))
    )
    (net (code "11") (name "Net-(U2K-EAVDD)") (class "Default")
      (node (ref "C91") (pin "2") (pinfunction "2_2") (pintype "passive"))
      (node (ref "C92") (pin "2") (pinfunction "2_2") (pintype "passive"))
      (node (ref "C93") (pin "2") (pinfunction "2_2") (pintype "passive"))
      (node (ref "L17") (pin "2") (pinfunction "2_2") (pintype "passive"))
      (node (ref "U2") (pin "AP28") (pinfunction "EAVDD_AP28") (pintype "input"))
    )
    (net (code "12") (name "Net-(U2K-UAVDD1)") (class "Default")
      (node (ref "C77") (pin "2") (pinfunction "2_2") (pintype "passive"))
      (node (ref "C78") (pin "2") (pinfunction "2_2") (pintype "passive"))
      (node (ref "C79") (pin "2") (pinfunction "2_2") (pintype "passive"))
      (node (ref "C80") (pin "2") (pinfunction "2_2") (pintype "passive"))
      (node (ref "L15") (pin "2") (pinfunction "2_2") (pintype "passive"))
      (node (ref "U2") (pin "L1") (pinfunction "UAVDD2_L1") (pintype "input"))
      (node (ref "U2") (pin "L2") (pinfunction "UAVDD1_L2") (pintype "input"))
    )
    (net (code "13") (name "Net-(U2K-UAVDD3)") (class "Default")
      (node (ref "C81") (pin "2") (pinfunction "2_2") (pintype "passive"))
      (node (ref "C82") (pin "2") (pinfunction "2_2") (pintype "passive"))
      (node (ref "C83") (pin "2") (pinfunction "2_2") (pintype "passive"))
      (node (ref "C84") (pin "2") (pinfunction "2_2") (pintype "passive"))
      (node (ref "L16") (pin "1") (pinfunction "1_1") (pintype "passive"))
      (node (ref "U2") (pin "J4") (pinfunction "UAVDD3_J4") (pintype "input"))
      (node (ref "U2") (pin "L4") (pinfunction "UAVDD4_L4") (pintype "input"))
    )
  )
)
